# Sheet1.net
KiCad netlist of a schematic drawn in Altium Designer
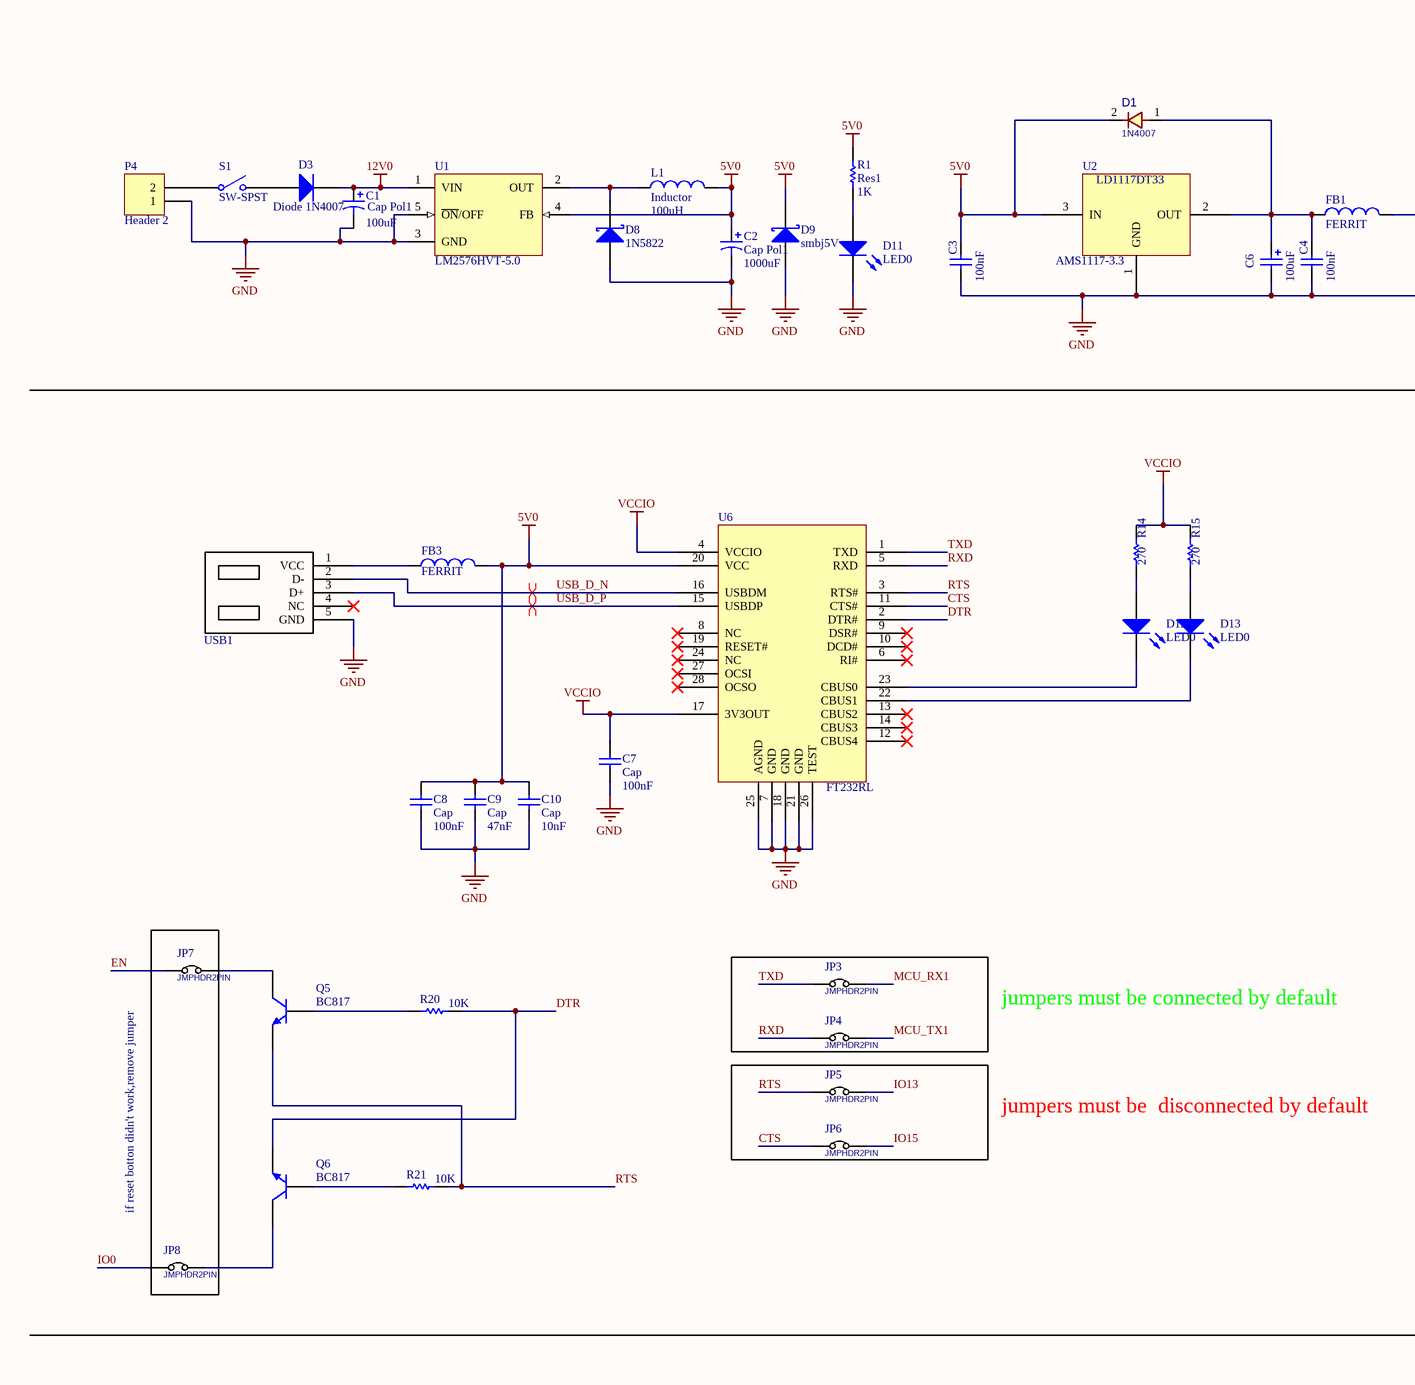
[diagram p0: Sheet1.SchDoc, top left]
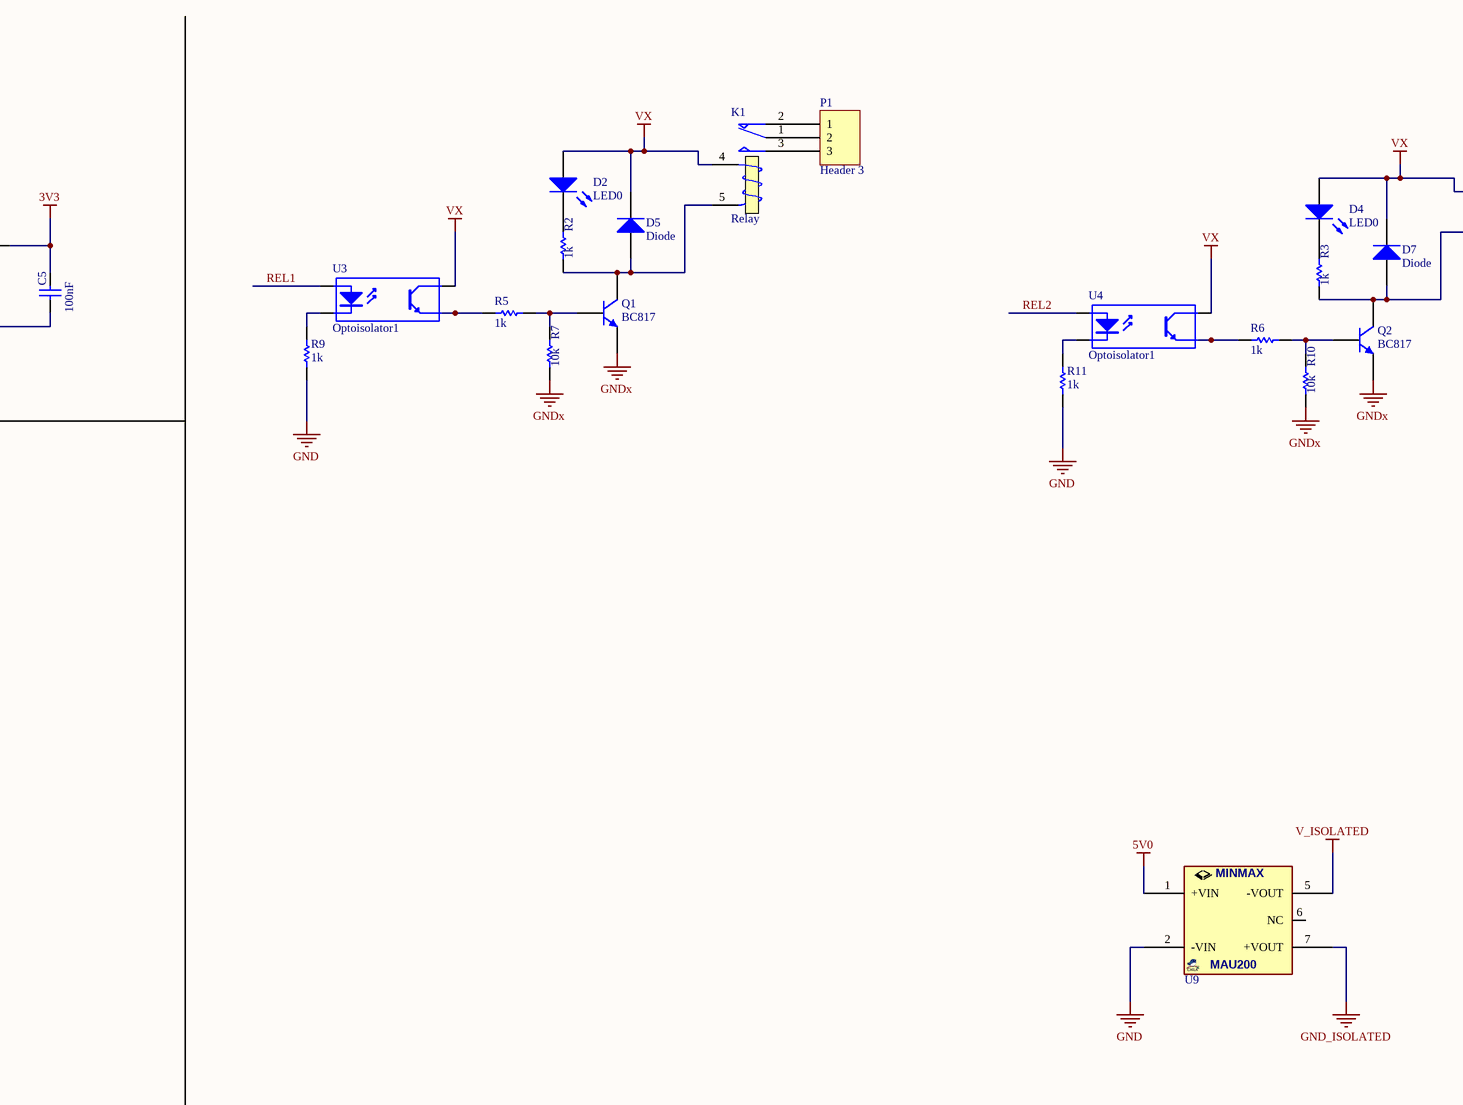
[diagram p1: Sheet1.SchDoc, top middle]
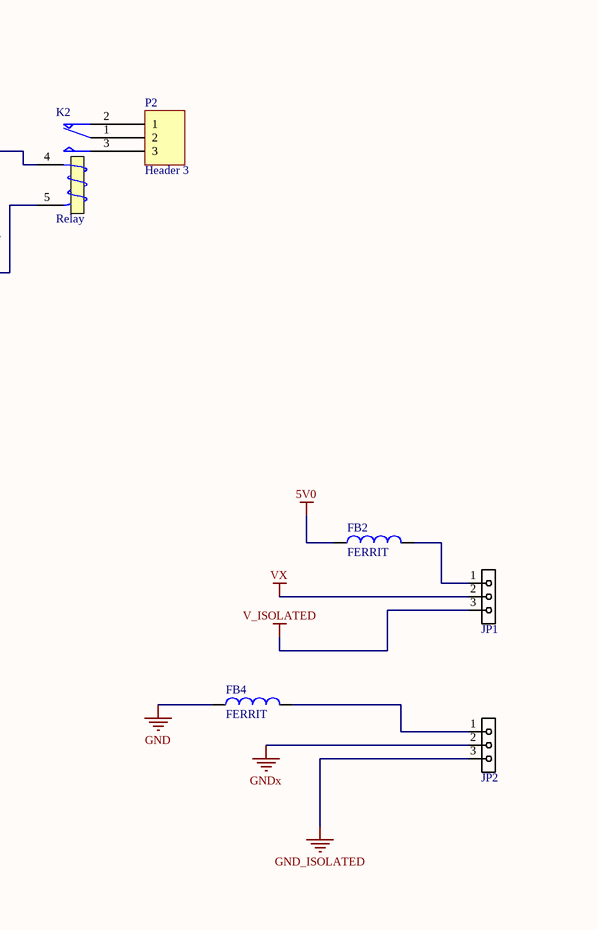
[diagram p2: Sheet1.SchDoc, top right]
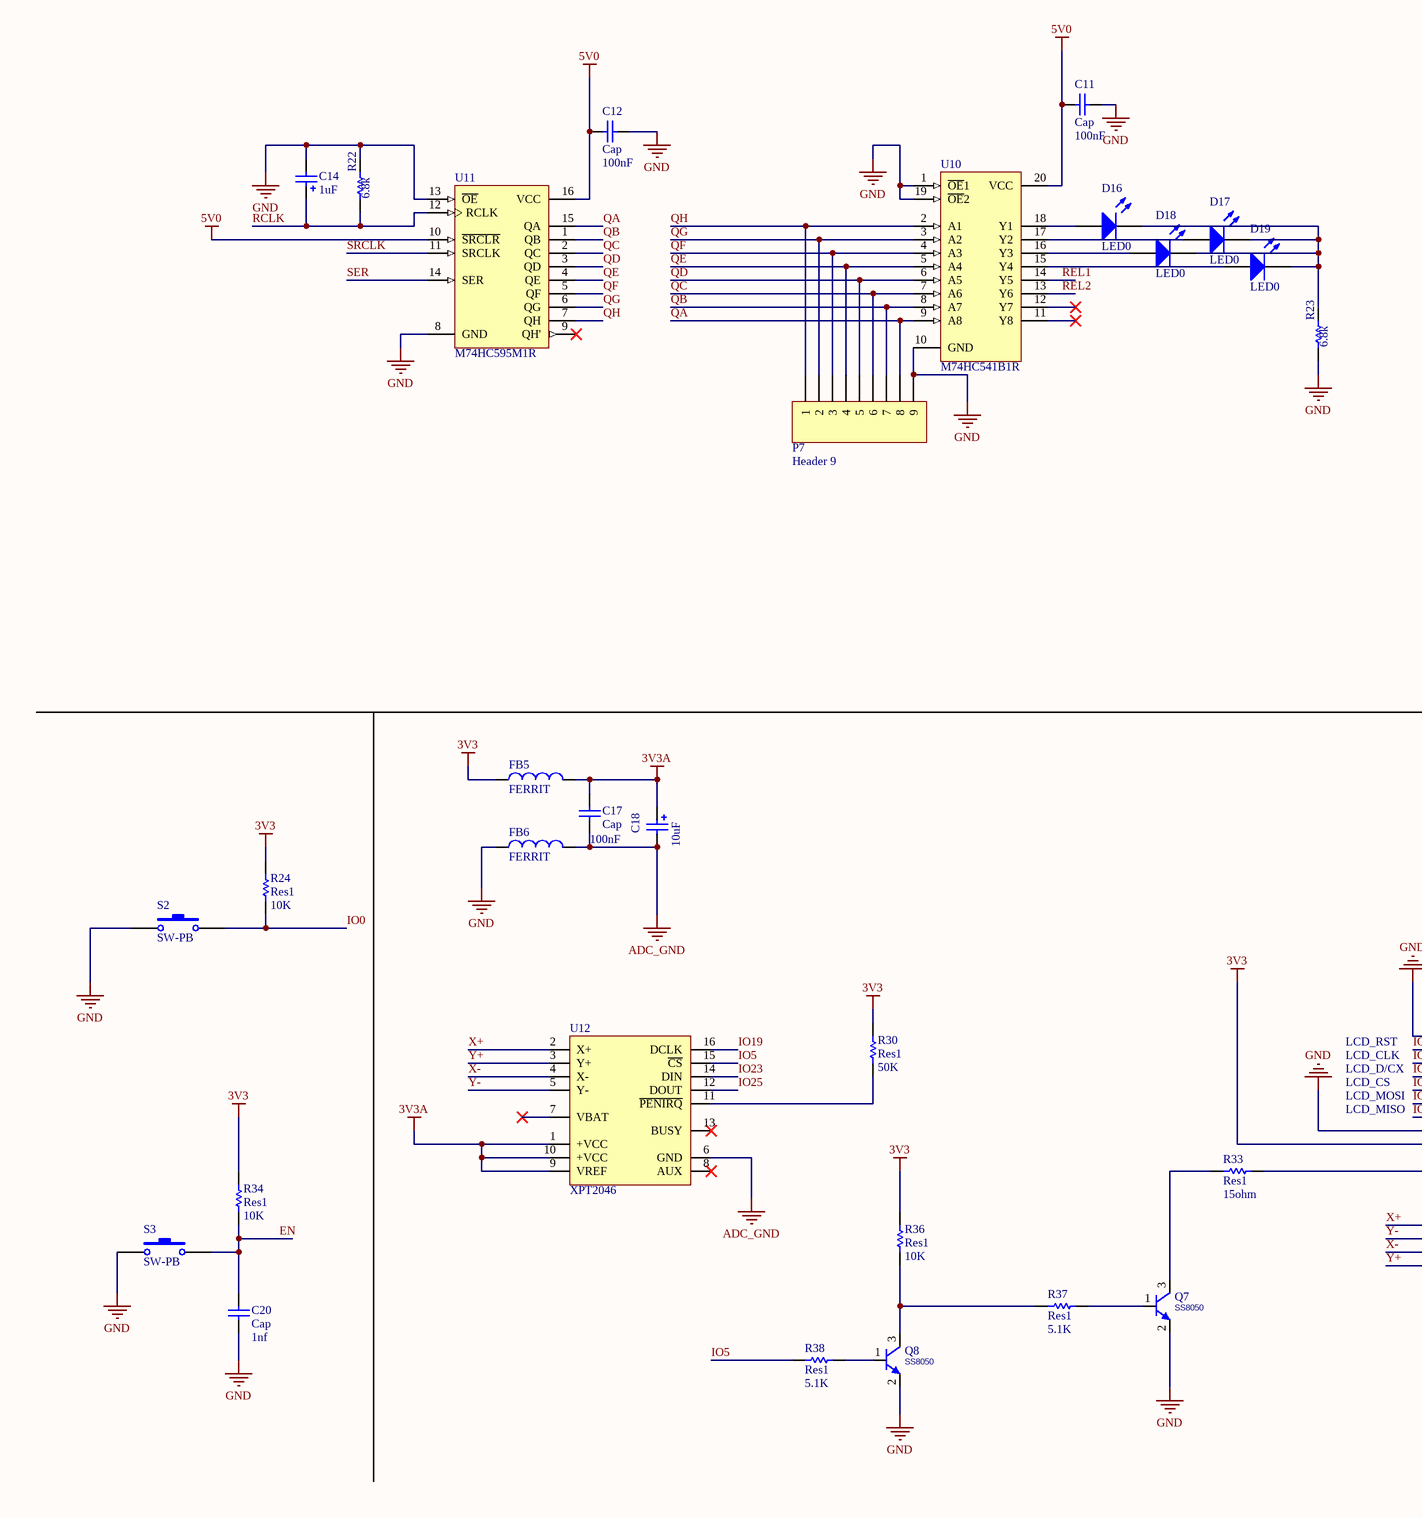
[diagram p3: Sheet1.SchDoc, bottom left]
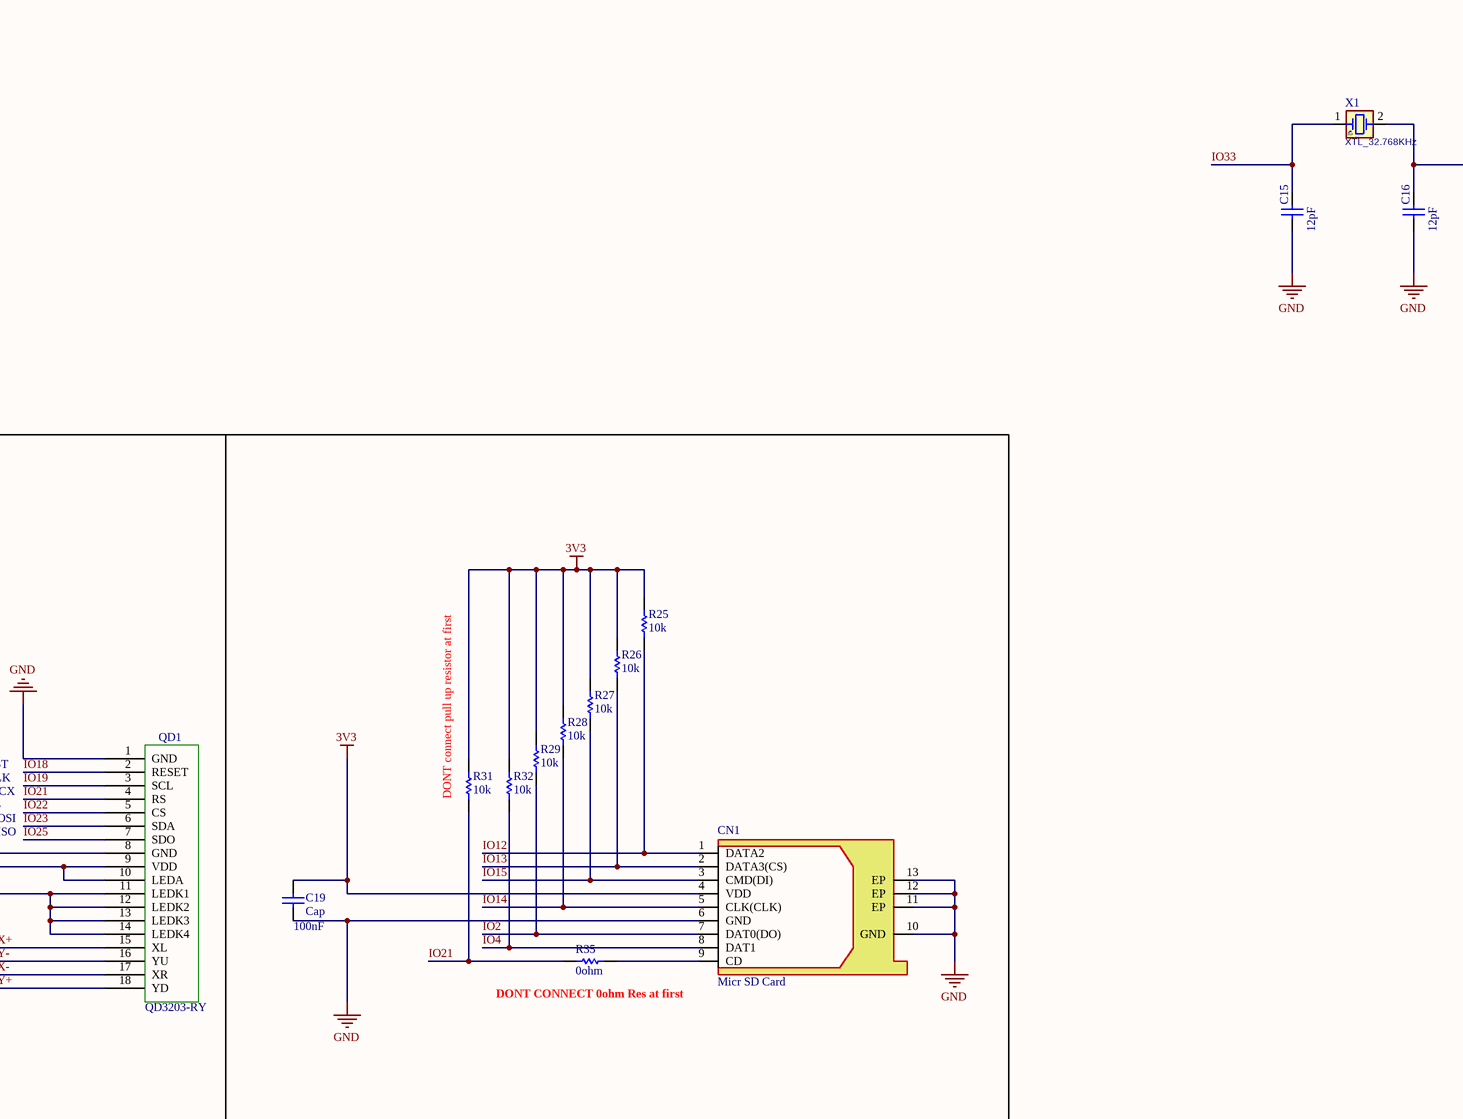
[diagram p4: Sheet1.SchDoc, bottom middle]
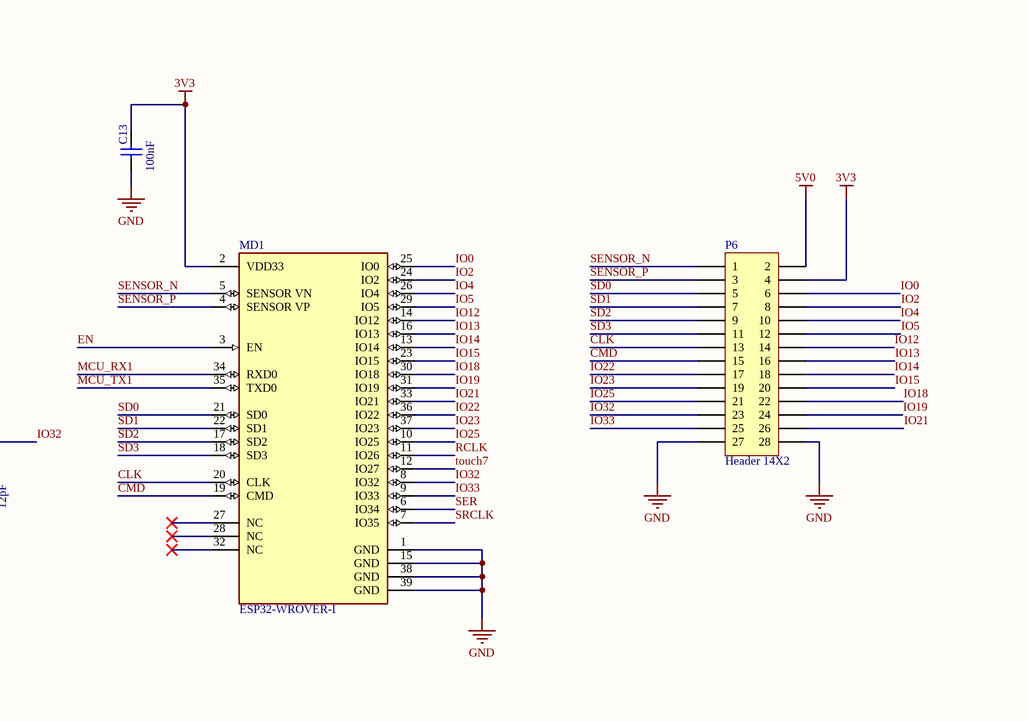
[diagram p5: Sheet1.SchDoc, bottom right]

(export (version "E")
  (design (tool "Eeschema 10.0.6"))
  (components
    (comp (ref "C1")
      (value "Cap Pol1")
      (footprint "C_CYL_SMD2")
      (description "Polarized Capacitor (Radial)")
      (fields (field (name "ALTIUM_VALUE") "100uF") (field (name "PUBLISHER") "Altium Limited"))
      (libsource (lib "Miscellaneous Devices") (part "Cap Pol1"))
    )
    (comp (ref "C2")
      (value "Cap Pol1")
      (footprint "C_CYL_SMD")
      (description "Polarized Capacitor (Radial)")
      (fields (field (name "ALTIUM_VALUE") "1000uF") (field (name "PUBLISHER") "Altium Limited"))
      (libsource (lib "Miscellaneous Devices") (part "Cap Pol1"))
    )
    (comp (ref "C3")
      (value "100nF")
      (footprint "SMD_805")
      (description "Capacitor")
      (fields (field (name "Comment") "Cap") (field (name "PUBLISHER") "Altium Limited"))
      (libsource (lib "Miscellaneous Devices") (part "Cap"))
    )
    (comp (ref "C4")
      (value "100nF")
      (footprint "SMD_805")
      (description "Capacitor")
      (fields (field (name "Comment") "Cap") (field (name "PUBLISHER") "Altium Limited"))
      (libsource (lib "Miscellaneous Devices") (part "Cap"))
    )
    (comp (ref "C5")
      (value "100nF")
      (footprint "SMD_805")
      (description "Capacitor")
      (fields (field (name "Comment") "Cap") (field (name "PUBLISHER") "Altium Limited"))
      (libsource (lib "Miscellaneous Devices") (part "Cap"))
    )
    (comp (ref "C6")
      (value "100uF")
      (footprint "C_B")
      (description "Polarized Capacitor (Axial)")
      (fields (field (name "Comment") "Cap Pol2") (field (name "PUBLISHER") "Altium Limited"))
      (libsource (lib "Miscellaneous Devices") (part "Cap Pol2"))
    )
    (comp (ref "C7")
      (value "Cap")
      (footprint "SMD_805")
      (description "Capacitor")
      (fields (field (name "ALTIUM_VALUE") "100nF") (field (name "PUBLISHER") "Altium Limited"))
      (libsource (lib "Miscellaneous Devices") (part "Cap"))
    )
    (comp (ref "C8")
      (value "Cap")
      (footprint "SMD_805")
      (description "Capacitor")
      (fields (field (name "ALTIUM_VALUE") "100nF") (field (name "PUBLISHER") "Altium Limited"))
      (libsource (lib "Miscellaneous Devices") (part "Cap"))
    )
    (comp (ref "C9")
      (value "Cap")
      (footprint "SMD_805")
      (description "Capacitor")
      (fields (field (name "ALTIUM_VALUE") "47nF") (field (name "PUBLISHER") "Altium Limited"))
      (libsource (lib "Miscellaneous Devices") (part "Cap"))
    )
    (comp (ref "C10")
      (value "Cap")
      (footprint "SMD_805")
      (description "Capacitor")
      (fields (field (name "ALTIUM_VALUE") "10nF") (field (name "PUBLISHER") "Altium Limited"))
      (libsource (lib "Miscellaneous Devices") (part "Cap"))
    )
    (comp (ref "C11")
      (value "Cap")
      (footprint "SMD_805")
      (description "Capacitor")
      (fields (field (name "ALTIUM_VALUE") "100nF") (field (name "PUBLISHER") "Altium Limited"))
      (libsource (lib "Miscellaneous Devices") (part "Cap"))
    )
    (comp (ref "C12")
      (value "Cap")
      (footprint "SMD_805")
      (description "Capacitor")
      (fields (field (name "ALTIUM_VALUE") "100nF") (field (name "PUBLISHER") "Altium Limited"))
      (libsource (lib "Miscellaneous Devices") (part "Cap"))
    )
    (comp (ref "C13")
      (value "100nF")
      (footprint "SMD_805")
      (description "Capacitor")
      (fields (field (name "Comment") "Cap") (field (name "PUBLISHER") "Altium Limited"))
      (libsource (lib "Miscellaneous Devices") (part "Cap"))
    )
    (comp (ref "C14")
      (value "1uF")
      (footprint "CAP_SMD_A")
      (description "Polarized Capacitor (Axial)")
      (fields (field (name "Comment") "Cap Pol2") (field (name "PUBLISHER") "Altium Limited"))
      (libsource (lib "Miscellaneous Devices") (part "Cap Pol2"))
    )
    (comp (ref "C15")
      (value "12pF")
      (footprint "SMD_805")
      (description "Capacitor")
      (fields (field (name "Comment") "Cap") (field (name "PUBLISHER") "Altium Limited"))
      (libsource (lib "Miscellaneous Devices") (part "Cap"))
    )
    (comp (ref "C16")
      (value "12pF")
      (footprint "SMD_805")
      (description "Capacitor")
      (fields (field (name "Comment") "Cap") (field (name "PUBLISHER") "Altium Limited"))
      (libsource (lib "Miscellaneous Devices") (part "Cap"))
    )
    (comp (ref "C17")
      (value "Cap")
      (footprint "SMD_805")
      (description "Capacitor")
      (fields (field (name "ALTIUM_VALUE") "100nF") (field (name "PUBLISHER") "Altium Limited"))
      (libsource (lib "Miscellaneous Devices") (part "Cap"))
    )
    (comp (ref "C18")
      (value "10uF")
      (footprint "C_B")
      (description "Polarized Capacitor (Axial)")
      (fields (field (name "Comment") "Cap Pol2") (field (name "PUBLISHER") "Altium Limited"))
      (libsource (lib "Miscellaneous Devices") (part "Cap Pol2"))
    )
    (comp (ref "C19")
      (value "Cap")
      (footprint "SMD_805")
      (description "Capacitor")
      (fields (field (name "ALTIUM_VALUE") "100nF") (field (name "PUBLISHER") "Altium Limited"))
      (libsource (lib "Miscellaneous Devices") (part "Cap"))
    )
    (comp (ref "C20")
      (value "Cap")
      (footprint "SMD_805")
      (description "Capacitor")
      (fields (field (name "ALTIUM_VALUE") "1nf") (field (name "PUBLISHER") "Altium Limited"))
      (libsource (lib "Miscellaneous Devices") (part "Cap"))
    )
    (comp (ref "CN1")
      (value "Micr SD Card")
      (footprint "Micro SD Card")
      (libsource (lib "ZetaBoard_Lib") (part "Micro SD Card"))
    )
    (comp (ref "D1")
      (value "1N4007")
      (footprint "D_SMA")
      (description "DIODE, GENERAL PURPOSE, 1000V/1A")
      (fields (field (name "MANF") "Kingtronics") (field (name "MANF_P#") "M7"))
      (libsource (lib "diode") (part "DIODE_SMD_1N4007"))
    )
    (comp (ref "D2")
      (value "LED0")
      (footprint "SMD_805")
      (description "Typical INFRARED GaAs LED")
      (fields (field (name "PUBLISHER") "Altium Limited"))
      (libsource (lib "ESP32_project") (part "LED0"))
    )
    (comp (ref "D3")
      (value "Diode 1N4007")
      (footprint "TVS")
      (description "1 Amp General Purpose Rectifier")
      (fields (field (name "PUBLISHER") "Altium Limited"))
      (libsource (lib "Miscellaneous Devices") (part "Diode 1N4007"))
    )
    (comp (ref "D4")
      (value "LED0")
      (footprint "SMD_805")
      (description "Typical INFRARED GaAs LED")
      (fields (field (name "PUBLISHER") "Altium Limited"))
      (libsource (lib "ESP32_project") (part "LED0"))
    )
    (comp (ref "D5")
      (value "Diode")
      (footprint "TVS")
      (description "Default Diode")
      (fields (field (name "PUBLISHER") "Altium Limited"))
      (libsource (lib "Miscellaneous Devices") (part "Diode"))
    )
    (comp (ref "D7")
      (value "Diode")
      (footprint "TVS")
      (description "Default Diode")
      (fields (field (name "PUBLISHER") "Altium Limited"))
      (libsource (lib "Miscellaneous Devices") (part "Diode"))
    )
    (comp (ref "D8")
      (value "1N5822")
      (footprint "DO_214_AB_SMC")
      (description "Schottky Rectifier")
      (fields (field (name "PUBLISHER") "Altium Limited"))
      (libsource (lib "Miscellaneous Devices") (part "Diode 11DQ03"))
    )
    (comp (ref "D9")
      (value "smbj5V")
      (footprint "DO_214_AB_SMC")
      (description "Schottky Rectifier")
      (fields (field (name "PUBLISHER") "Altium Limited"))
      (libsource (lib "Miscellaneous Devices") (part "Diode 11DQ03"))
    )
    (comp (ref "D11")
      (value "LED0")
      (footprint "SMD_805")
      (description "Typical INFRARED GaAs LED")
      (fields (field (name "PUBLISHER") "Altium Limited"))
      (libsource (lib "ESP32_project") (part "LED0"))
    )
    (comp (ref "D12")
      (value "LED0")
      (footprint "SMD_805")
      (description "Typical INFRARED GaAs LED")
      (fields (field (name "PUBLISHER") "Altium Limited"))
      (libsource (lib "ESP32_project") (part "LED0"))
    )
    (comp (ref "D13")
      (value "LED0")
      (footprint "SMD_805")
      (description "Typical INFRARED GaAs LED")
      (fields (field (name "PUBLISHER") "Altium Limited"))
      (libsource (lib "ESP32_project") (part "LED0"))
    )
    (comp (ref "D16")
      (value "LED0")
      (footprint "SMD_805")
      (description "Typical INFRARED GaAs LED")
      (fields (field (name "PUBLISHER") "Altium Limited"))
      (libsource (lib "ESP32_project") (part "LED0"))
    )
    (comp (ref "D17")
      (value "LED0")
      (footprint "SMD_805")
      (description "Typical INFRARED GaAs LED")
      (fields (field (name "PUBLISHER") "Altium Limited"))
      (libsource (lib "ESP32_project") (part "LED0"))
    )
    (comp (ref "D18")
      (value "LED0")
      (footprint "SMD_805")
      (description "Typical INFRARED GaAs LED")
      (fields (field (name "PUBLISHER") "Altium Limited"))
      (libsource (lib "ESP32_project") (part "LED0"))
    )
    (comp (ref "D19")
      (value "LED0")
      (footprint "SMD_805")
      (description "Typical INFRARED GaAs LED")
      (fields (field (name "PUBLISHER") "Altium Limited"))
      (libsource (lib "ESP32_project") (part "LED0"))
    )
    (comp (ref "FB1")
      (value "FERRIT")
      (footprint "SMD_805")
      (description "Inductor")
      (fields (field (name "PUBLISHER") "Altium Limited"))
      (libsource (lib "Miscellaneous Devices") (part "Inductor"))
    )
    (comp (ref "FB2")
      (value "FERRIT")
      (footprint "SMD_805")
      (description "Inductor")
      (fields (field (name "PUBLISHER") "Altium Limited"))
      (libsource (lib "Miscellaneous Devices") (part "Inductor"))
    )
    (comp (ref "FB3")
      (value "FERRIT")
      (footprint "SMD_805")
      (description "Inductor")
      (fields (field (name "PUBLISHER") "Altium Limited"))
      (libsource (lib "Miscellaneous Devices") (part "Inductor"))
    )
    (comp (ref "FB4")
      (value "FERRIT")
      (footprint "SMD_805")
      (description "Inductor")
      (fields (field (name "PUBLISHER") "Altium Limited"))
      (libsource (lib "Miscellaneous Devices") (part "Inductor"))
    )
    (comp (ref "FB5")
      (value "FERRIT")
      (footprint "SMD_805")
      (description "Inductor")
      (fields (field (name "PUBLISHER") "Altium Limited"))
      (libsource (lib "Miscellaneous Devices") (part "Inductor"))
    )
    (comp (ref "FB6")
      (value "FERRIT")
      (footprint "SMD_805")
      (description "Inductor")
      (fields (field (name "PUBLISHER") "Altium Limited"))
      (libsource (lib "Miscellaneous Devices") (part "Inductor"))
    )
    (comp (ref "JP1")
      (value "JMPHDR3PIN")
      (footprint "JP_3")
      (description "JUMPER, HEADER 3PIN")
      (fields (field (name "MANF") "MANF") (field (name "MANF_P#") "MANF_P#"))
      (libsource (lib "test-tp_jumper") (part "JUMPER_HDR_3P"))
    )
    (comp (ref "JP2")
      (value "JMPHDR3PIN")
      (footprint "JP_3")
      (description "JUMPER, HEADER 3PIN")
      (fields (field (name "MANF") "MANF") (field (name "MANF_P#") "MANF_P#"))
      (libsource (lib "test-tp_jumper") (part "JUMPER_HDR_3P"))
    )
    (comp (ref "JP3")
      (value "JMPHDR2PIN")
      (footprint "JP_2_BLK")
      (description "JUMPER, HEADER 2PIN")
      (fields (field (name "MANF") "MANF") (field (name "MANF_P#") "MANF_P#"))
      (libsource (lib "test-tp_jumper") (part "JUMPER_HDR_2P"))
    )
    (comp (ref "JP4")
      (value "JMPHDR2PIN")
      (footprint "JP_2_BLK")
      (description "JUMPER, HEADER 2PIN")
      (fields (field (name "MANF") "MANF") (field (name "MANF_P#") "MANF_P#"))
      (libsource (lib "test-tp_jumper") (part "JUMPER_HDR_2P"))
    )
    (comp (ref "JP5")
      (value "JMPHDR2PIN")
      (footprint "JP_2_BLK")
      (description "JUMPER, HEADER 2PIN")
      (fields (field (name "MANF") "MANF") (field (name "MANF_P#") "MANF_P#"))
      (libsource (lib "test-tp_jumper") (part "JUMPER_HDR_2P"))
    )
    (comp (ref "JP6")
      (value "JMPHDR2PIN")
      (footprint "JP_2_BLK")
      (description "JUMPER, HEADER 2PIN")
      (fields (field (name "MANF") "MANF") (field (name "MANF_P#") "MANF_P#"))
      (libsource (lib "test-tp_jumper") (part "JUMPER_HDR_2P"))
    )
    (comp (ref "JP7")
      (value "JMPHDR2PIN")
      (footprint "JP_2_BLK")
      (description "JUMPER, HEADER 2PIN")
      (fields (field (name "MANF") "MANF") (field (name "MANF_P#") "MANF_P#"))
      (libsource (lib "test-tp_jumper") (part "JUMPER_HDR_2P"))
    )
    (comp (ref "JP8")
      (value "JMPHDR2PIN")
      (footprint "JP_2_BLK")
      (description "JUMPER, HEADER 2PIN")
      (fields (field (name "MANF") "MANF") (field (name "MANF_P#") "MANF_P#"))
      (libsource (lib "test-tp_jumper") (part "JUMPER_HDR_2P"))
    )
    (comp (ref "K1")
      (value "Relay")
      (footprint "RELAY_5V")
      (description "SPDT Relay")
      (fields (field (name "PUBLISHER") "Altium Limited"))
      (libsource (lib "Miscellaneous Devices") (part "Relay"))
    )
    (comp (ref "K2")
      (value "Relay")
      (footprint "RELAY_5V")
      (description "SPDT Relay")
      (fields (field (name "PUBLISHER") "Altium Limited"))
      (libsource (lib "Miscellaneous Devices") (part "Relay"))
    )
    (comp (ref "L1")
      (value "Inductor")
      (footprint "INDUC_SMD")
      (fields (field (name "ALTIUM_VALUE") "100uH") (field (name "PUBLISHER") "Altium Limited"))
      (libsource (lib "Miscellaneous Devices") (part "Inductor"))
    )
    (comp (ref "MD1")
      (value "ESP32-WROVER-I")
      (footprint "FP-ESP32-WROVER-I-MFG")
      (description "SMD MODULE, ESP32-D0WDQ6, 32MBIT")
      (fields
        (field (name "MANUFACTURER") "Espressif")
        (field (name "OCTOPART") "https://octopart.com/esp32-wrover-i-espressif+systems-89171349")
      )
      (libsource (lib "Altium Content Vault") (part "cbbb37af8bcfe61dfd46ac9418f0340"))
    )
    (comp (ref "P1")
      (value "Header 3")
      (footprint "PHOENIX_3")
      (description "Header, 3-Pin")
      (fields (field (name "PUBLISHER") "Altium Limited"))
      (libsource (lib "Miscellaneous Connectors") (part "Header 3"))
    )
    (comp (ref "P2")
      (value "Header 3")
      (footprint "PHOENIX_3")
      (description "Header, 3-Pin")
      (fields (field (name "PUBLISHER") "Altium Limited"))
      (libsource (lib "Miscellaneous Connectors") (part "Header 3"))
    )
    (comp (ref "P4")
      (value "Header 2")
      (footprint "adap_jack")
      (description "Header, 2-Pin")
      (fields (field (name "PUBLISHER") "Altium Limited"))
      (libsource (lib "Miscellaneous Connectors") (part "Header 2"))
    )
    (comp (ref "P6")
      (value "Header 14X2")
      (footprint "HDR2X14")
      (description "Header, 14-Pin, Dual row")
      (fields (field (name "PUBLISHER") "Altium Limited"))
      (libsource (lib "Miscellaneous Connectors") (part "Header 14X2"))
    )
    (comp (ref "P7")
      (value "Header 9")
      (footprint "ARAY 9")
      (description "Header, 9-Pin")
      (fields (field (name "PUBLISHER") "Altium Limited"))
      (libsource (lib "Miscellaneous Connectors") (part "Header 9"))
    )
    (comp (ref "Q1")
      (value "BC817")
      (footprint "SOT23")
      (description "NPN General Purpose Amplifier")
      (fields (field (name "PUBLISHER") "Altium Limited"))
      (libsource (lib "Miscellaneous Devices") (part "2N3904"))
    )
    (comp (ref "Q2")
      (value "BC817")
      (footprint "SOT23")
      (description "NPN General Purpose Amplifier")
      (fields (field (name "PUBLISHER") "Altium Limited"))
      (libsource (lib "Miscellaneous Devices") (part "2N3904"))
    )
    (comp (ref "Q5")
      (value "BC817")
      (footprint "SOT23")
      (description "NPN General Purpose Amplifier")
      (fields (field (name "PUBLISHER") "Altium Limited"))
      (libsource (lib "Miscellaneous Devices") (part "2N3904"))
    )
    (comp (ref "Q6")
      (value "BC817")
      (footprint "SOT23")
      (description "NPN General Purpose Amplifier")
      (fields (field (name "PUBLISHER") "Altium Limited"))
      (libsource (lib "Miscellaneous Devices") (part "2N3904"))
    )
    (comp (ref "Q7")
      (value "SS8050")
      (footprint "SOT23_3")
      (description "BJT, NPN, 25v, 1.5A, SMD, SOT23")
      (fields (field (name "MANF") "GALAXY"))
      (libsource (lib "transistor_bjt") (part "NPN_SS8050_SOT23"))
    )
    (comp (ref "Q8")
      (value "SS8050")
      (footprint "SOT23_3")
      (description "BJT, NPN, 25v, 1.5A, SMD, SOT23")
      (fields (field (name "MANF") "GALAXY"))
      (libsource (lib "transistor_bjt") (part "NPN_SS8050_SOT23"))
    )
    (comp (ref "QD1")
      (value "QD3203-RY")
      (footprint "QD-TFT2803")
      (libsource (lib "2.8inch_MSP2807_Schematic_Package_Library") (part "FPC240A8230-V1-E"))
    )
    (comp (ref "R1")
      (value "Res1")
      (footprint "SMD_805")
      (description "Resistor")
      (fields (field (name "ALTIUM_VALUE") "1K") (field (name "PUBLISHER") "Altium Limited"))
      (libsource (lib "Miscellaneous Devices") (part "Res1"))
    )
    (comp (ref "R2")
      (value "1k")
      (footprint "SMD_805")
      (description "Resistor")
      (fields (field (name "Comment") "Res1") (field (name "PUBLISHER") "Altium Limited"))
      (libsource (lib "Miscellaneous Devices") (part "Res1"))
    )
    (comp (ref "R3")
      (value "1k")
      (footprint "SMD_805")
      (description "Resistor")
      (fields (field (name "Comment") "Res1") (field (name "PUBLISHER") "Altium Limited"))
      (libsource (lib "Miscellaneous Devices") (part "Res1"))
    )
    (comp (ref "R5")
      (value "1k")
      (footprint "SMD_805")
      (description "Resistor")
      (fields (field (name "Comment") "Res1") (field (name "PUBLISHER") "Altium Limited"))
      (libsource (lib "Miscellaneous Devices") (part "Res1"))
    )
    (comp (ref "R6")
      (value "1k")
      (footprint "SMD_805")
      (description "Resistor")
      (fields (field (name "Comment") "Res1") (field (name "PUBLISHER") "Altium Limited"))
      (libsource (lib "Miscellaneous Devices") (part "Res1"))
    )
    (comp (ref "R7")
      (value "10k")
      (footprint "SMD_805")
      (description "Resistor")
      (fields (field (name "Comment") "Res1") (field (name "PUBLISHER") "Altium Limited"))
      (libsource (lib "Miscellaneous Devices") (part "Res1"))
    )
    (comp (ref "R9")
      (value "1k")
      (footprint "SMD_805")
      (description "Resistor")
      (fields (field (name "Comment") "Res1") (field (name "PUBLISHER") "Altium Limited"))
      (libsource (lib "Miscellaneous Devices") (part "Res1"))
    )
    (comp (ref "R10")
      (value "10k")
      (footprint "SMD_805")
      (description "Resistor")
      (fields (field (name "Comment") "Res1") (field (name "PUBLISHER") "Altium Limited"))
      (libsource (lib "Miscellaneous Devices") (part "Res1"))
    )
    (comp (ref "R11")
      (value "1k")
      (footprint "SMD_805")
      (description "Resistor")
      (fields (field (name "Comment") "Res1") (field (name "PUBLISHER") "Altium Limited"))
      (libsource (lib "Miscellaneous Devices") (part "Res1"))
    )
    (comp (ref "R14")
      (value "270")
      (footprint "SMD_805")
      (description "Resistor")
      (fields (field (name "Comment") "Res1") (field (name "PUBLISHER") "Altium Limited"))
      (libsource (lib "Miscellaneous Devices") (part "Res1"))
    )
    (comp (ref "R15")
      (value "270")
      (footprint "SMD_805")
      (description "Resistor")
      (fields (field (name "Comment") "Res1") (field (name "PUBLISHER") "Altium Limited"))
      (libsource (lib "Miscellaneous Devices") (part "Res1"))
    )
    (comp (ref "R20")
      (value "10K")
      (footprint "SMD_805")
      (description "Resistor")
      (fields (field (name "Comment") "Res1") (field (name "PUBLISHER") "Altium Limited"))
      (libsource (lib "Miscellaneous Devices") (part "Res1"))
    )
    (comp (ref "R21")
      (value "10K")
      (footprint "SMD_805")
      (description "Resistor")
      (fields (field (name "Comment") "Res1") (field (name "PUBLISHER") "Altium Limited"))
      (libsource (lib "Miscellaneous Devices") (part "Res1"))
    )
    (comp (ref "R22")
      (value "6.8k")
      (footprint "SMD_805")
      (description "Resistor")
      (fields (field (name "Comment") "Res1") (field (name "PUBLISHER") "Altium Limited"))
      (libsource (lib "Miscellaneous Devices") (part "Res1"))
    )
    (comp (ref "R23")
      (value "6.8k")
      (footprint "SMD_805")
      (description "Resistor")
      (fields (field (name "Comment") "Res1") (field (name "PUBLISHER") "Altium Limited"))
      (libsource (lib "Miscellaneous Devices") (part "Res1"))
    )
    (comp (ref "R24")
      (value "Res1")
      (footprint "SMD_805")
      (description "Resistor")
      (fields (field (name "ALTIUM_VALUE") "10K") (field (name "PUBLISHER") "Altium Limited"))
      (libsource (lib "Miscellaneous Devices") (part "Res1"))
    )
    (comp (ref "R25")
      (value "10k")
      (footprint "SMD_805")
      (description "Resistor")
      (fields (field (name "Comment") "Res1") (field (name "PUBLISHER") "Altium Limited"))
      (libsource (lib "Miscellaneous Devices") (part "Res1"))
    )
    (comp (ref "R26")
      (value "10k")
      (footprint "SMD_805")
      (description "Resistor")
      (fields (field (name "Comment") "Res1") (field (name "PUBLISHER") "Altium Limited"))
      (libsource (lib "Miscellaneous Devices") (part "Res1"))
    )
    (comp (ref "R27")
      (value "10k")
      (footprint "SMD_805")
      (description "Resistor")
      (fields (field (name "Comment") "Res1") (field (name "PUBLISHER") "Altium Limited"))
      (libsource (lib "Miscellaneous Devices") (part "Res1"))
    )
    (comp (ref "R28")
      (value "10k")
      (footprint "SMD_805")
      (description "Resistor")
      (fields (field (name "Comment") "Res1") (field (name "PUBLISHER") "Altium Limited"))
      (libsource (lib "Miscellaneous Devices") (part "Res1"))
    )
    (comp (ref "R29")
      (value "10k")
      (footprint "SMD_805")
      (description "Resistor")
      (fields (field (name "Comment") "Res1") (field (name "PUBLISHER") "Altium Limited"))
      (libsource (lib "Miscellaneous Devices") (part "Res1"))
    )
    (comp (ref "R30")
      (value "Res1")
      (footprint "SMD_805")
      (description "Resistor")
      (fields (field (name "ALTIUM_VALUE") "50K") (field (name "PUBLISHER") "Altium Limited"))
      (libsource (lib "Miscellaneous Devices") (part "Res1"))
    )
    (comp (ref "R31")
      (value "10k")
      (footprint "SMD_805")
      (description "Resistor")
      (fields (field (name "Comment") "Res1") (field (name "PUBLISHER") "Altium Limited"))
      (libsource (lib "Miscellaneous Devices") (part "Res1"))
    )
    (comp (ref "R32")
      (value "10k")
      (footprint "SMD_805")
      (description "Resistor")
      (fields (field (name "Comment") "Res1") (field (name "PUBLISHER") "Altium Limited"))
      (libsource (lib "Miscellaneous Devices") (part "Res1"))
    )
    (comp (ref "R33")
      (value "Res1")
      (footprint "SMD_805")
      (description "Resistor")
      (fields (field (name "ALTIUM_VALUE") "15ohm") (field (name "PUBLISHER") "Altium Limited"))
      (libsource (lib "Miscellaneous Devices") (part "Res1"))
    )
    (comp (ref "R34")
      (value "Res1")
      (footprint "SMD_805")
      (description "Resistor")
      (fields (field (name "ALTIUM_VALUE") "10K") (field (name "PUBLISHER") "Altium Limited"))
      (libsource (lib "Miscellaneous Devices") (part "Res1"))
    )
    (comp (ref "R35")
      (value "0ohm")
      (footprint "SMD_805")
      (description "Resistor")
      (fields (field (name "Comment") "Res1") (field (name "PUBLISHER") "Altium Limited"))
      (libsource (lib "Miscellaneous Devices") (part "Res1"))
    )
    (comp (ref "R36")
      (value "Res1")
      (footprint "SMD_805")
      (description "Resistor")
      (fields (field (name "ALTIUM_VALUE") "10K") (field (name "PUBLISHER") "Altium Limited"))
      (libsource (lib "Miscellaneous Devices") (part "Res1"))
    )
    (comp (ref "R37")
      (value "Res1")
      (footprint "SMD_805")
      (description "Resistor")
      (fields (field (name "ALTIUM_VALUE") "5.1K") (field (name "PUBLISHER") "Altium Limited"))
      (libsource (lib "Miscellaneous Devices") (part "Res1"))
    )
    (comp (ref "R38")
      (value "Res1")
      (footprint "SMD_805")
      (description "Resistor")
      (fields (field (name "ALTIUM_VALUE") "5.1K") (field (name "PUBLISHER") "Altium Limited"))
      (libsource (lib "Miscellaneous Devices") (part "Res1"))
    )
    (comp (ref "S1")
      (value "SW-SPST")
      (footprint "KEY1")
      (description "Single-Pole, Single-Throw Switch")
      (fields (field (name "PUBLISHER") "Altium Limited"))
      (libsource (lib "Miscellaneous Devices") (part "SW-SPST"))
    )
    (comp (ref "S2")
      (value "SW-PB")
      (footprint "smd_button")
      (description "Switch")
      (fields (field (name "PUBLISHER") "Altium Limited"))
      (libsource (lib "Miscellaneous Devices") (part "SW-PB"))
    )
    (comp (ref "S3")
      (value "SW-PB")
      (footprint "smd_button")
      (description "Switch")
      (fields (field (name "PUBLISHER") "Altium Limited"))
      (libsource (lib "Miscellaneous Devices") (part "SW-PB"))
    )
    (comp (ref "U1")
      (value "LM2576HVT-5.0")
      (footprint "TO - 263")
      (description "SIMPLE SWITCHER; 3A Step-Down Voltage Regulator")
      (fields
        (field (name "MANUFACTURER") "National Semiconductor")
        (field (name "DIGIKEYPARTNUMBER") "LM2576HVT-5.0-ND")
        (field (name "PUBLISHER") "Altium Limited")
      )
      (libsource (lib "NSC Switcher") (part "LM2576HVT-5.0"))
    )
    (comp (ref "U2")
      (value "AMS1117-3.3")
      (footprint "SOT223")
      (libsource (lib "LD1117DT33") (part "LD1117DT33"))
    )
    (comp (ref "U3")
      (value "Optoisolator1")
      (footprint "PC817_SMD")
      (description "4-Pin Phototransistor Optocoupler")
      (fields (field (name "PUBLISHER") "Altium Limited"))
      (libsource (lib "Miscellaneous Devices") (part "Optoisolator1"))
    )
    (comp (ref "U4")
      (value "Optoisolator1")
      (footprint "PC817_SMD")
      (description "4-Pin Phototransistor Optocoupler")
      (fields (field (name "PUBLISHER") "Altium Limited"))
      (libsource (lib "Miscellaneous Devices") (part "Optoisolator1"))
    )
    (comp (ref "U6") (value "FT232RL") (footprint "SOG65_28_W") (libsource (lib "FT232RL") (part "FT232RL")))
    (comp (ref "U9")
      (value "MAU202")
      (footprint "MINMAX_MAU200")
      (description "DC-DC Converter, Isolated, 1W")
      (fields (field (name "MANF") "MINMAX"))
      (libsource (lib "module_dc2dc_iso") (part "MAU202"))
    )
    (comp (ref "U10")
      (value "M74HC541B1R")
      (footprint "SOP20")
      (description "Octal Bus Buffer with 3 State Outputs (Non Inverted)")
      (fields (field (name "PUBLISHER") "Altium Limited"))
      (libsource (lib "ST Logic Buffer Line Driver") (part "M74HC541B1R"))
    )
    (comp (ref "U11")
      (value "M74HC595M1R")
      (footprint "SO16_L")
      (description "8 Bit Shift Register with Output Latches (3 STATE)")
      (fields (field (name "PUBLISHER") "Altium Limited"))
      (libsource (lib "ST Logic Register") (part "M74HC595M1R"))
    )
    (comp (ref "U12")
      (value "XPT2046")
      (footprint "TSSOP-16")
      (libsource (lib "ZetaBoard_Lib") (part "XPT2046"))
    )
    (comp (ref "USB1")
      (value "MICRO_USB")
      (footprint "MINI_USB")
      (libsource (lib "MICRO_USB") (part "MICRO_USB"))
    )
    (comp (ref "X1")
      (value "XTL_32.768KHz")
      (footprint "XTL_2_1610")
      (description "Crystal, 32.768KHz, 9pF, 20PPM")
      (fields (field (name "MANF") "ABRACON") (field (name "MANF_P#") "ABS05-32.768KHZ-9-T"))
      (libsource (lib "crystal") (part "XTL_2_32.768_1610A"))
    )
  )
  (nets
    (net (code "1") (name "/CLK") (class "Default")
      (node (ref "MD1") (pin "20") (pinfunction "CLK_20") (pintype "bidirectional"))
      (node (ref "P6") (pin "13") (pinfunction "13_13") (pintype "passive"))
    )
    (net (code "2") (name "/CMD") (class "Default")
      (node (ref "MD1") (pin "19") (pinfunction "CMD_19") (pintype "bidirectional"))
      (node (ref "P6") (pin "15") (pinfunction "15_15") (pintype "passive"))
    )
    (net (code "3") (name "/CTS") (class "Default")
      (node (ref "JP6") (pin "1") (pinfunction "1_1") (pintype "passive"))
      (node (ref "U6") (pin "11") (pinfunction "CTS#_11") (pintype "passive"))
    )
    (net (code "4") (name "/DTR") (class "Default")
      (node (ref "Q6") (pin "2") (pinfunction "E_2") (pintype "passive"))
      (node (ref "R20") (pin "1") (pinfunction "1_1") (pintype "passive"))
      (node (ref "U6") (pin "2") (pinfunction "DTR#_2") (pintype "passive"))
    )
    (net (code "5") (name "/EN") (class "Default")
      (node (ref "C20") (pin "2") (pinfunction "2_2") (pintype "passive"))
      (node (ref "JP7") (pin "1") (pinfunction "1_1") (pintype "passive"))
      (node (ref "MD1") (pin "3") (pinfunction "EN_3") (pintype "input"))
      (node (ref "R34") (pin "1") (pinfunction "1_1") (pintype "passive"))
      (node (ref "S3") (pin "2") (pinfunction "2_2") (pintype "passive"))
    )
    (net (code "6") (name "/IO0") (class "Default")
      (node (ref "JP8") (pin "1") (pinfunction "1_1") (pintype "passive"))
      (node (ref "MD1") (pin "25") (pinfunction "IO0_25") (pintype "bidirectional"))
      (node (ref "P6") (pin "6") (pinfunction "6_6") (pintype "passive"))
      (node (ref "R24") (pin "1") (pinfunction "1_1") (pintype "passive"))
      (node (ref "S2") (pin "2") (pinfunction "2_2") (pintype "passive"))
    )
    (net (code "7") (name "/IO2") (class "Default")
      (node (ref "CN1") (pin "7") (pinfunction "DAT0(DO)_7") (pintype "passive"))
      (node (ref "MD1") (pin "24") (pinfunction "IO2_24") (pintype "bidirectional"))
      (node (ref "P6") (pin "8") (pinfunction "8_8") (pintype "passive"))
      (node (ref "R29") (pin "2") (pinfunction "2_2") (pintype "passive"))
    )
    (net (code "8") (name "/IO4") (class "Default")
      (node (ref "CN1") (pin "8") (pinfunction "DAT1_8") (pintype "passive"))
      (node (ref "MD1") (pin "26") (pinfunction "IO4_26") (pintype "bidirectional"))
      (node (ref "P6") (pin "10") (pinfunction "10_10") (pintype "passive"))
      (node (ref "R32") (pin "2") (pinfunction "2_2") (pintype "passive"))
    )
    (net (code "9") (name "/IO5") (class "Default")
      (node (ref "MD1") (pin "29") (pinfunction "IO5_29") (pintype "bidirectional"))
      (node (ref "P6") (pin "12") (pinfunction "12_12") (pintype "passive"))
      (node (ref "R38") (pin "2") (pinfunction "2_2") (pintype "passive"))
      (node (ref "U12") (pin "15") (pinfunction "~{CS}_15") (pintype "passive"))
    )
    (net (code "10") (name "/IO12") (class "Default")
      (node (ref "CN1") (pin "1") (pinfunction "DATA2_1") (pintype "passive"))
      (node (ref "MD1") (pin "14") (pinfunction "IO12_14") (pintype "bidirectional"))
      (node (ref "P6") (pin "14") (pinfunction "14_14") (pintype "passive"))
      (node (ref "R25") (pin "2") (pinfunction "2_2") (pintype "passive"))
    )
    (net (code "11") (name "/IO13") (class "Default")
      (node (ref "CN1") (pin "2") (pinfunction "DATA3(CS)_2") (pintype "passive"))
      (node (ref "JP5") (pin "2") (pinfunction "2_2") (pintype "passive"))
      (node (ref "MD1") (pin "16") (pinfunction "IO13_16") (pintype "bidirectional"))
      (node (ref "P6") (pin "16") (pinfunction "16_16") (pintype "passive"))
      (node (ref "R26") (pin "2") (pinfunction "2_2") (pintype "passive"))
    )
    (net (code "12") (name "/IO14") (class "Default")
      (node (ref "CN1") (pin "5") (pinfunction "CLK(CLK)_5") (pintype "passive"))
      (node (ref "MD1") (pin "13") (pinfunction "IO14_13") (pintype "bidirectional"))
      (node (ref "P6") (pin "18") (pinfunction "18_18") (pintype "passive"))
      (node (ref "R28") (pin "2") (pinfunction "2_2") (pintype "passive"))
    )
    (net (code "13") (name "/IO15") (class "Default")
      (node (ref "CN1") (pin "3") (pinfunction "CMD(DI)_3") (pintype "passive"))
      (node (ref "JP6") (pin "2") (pinfunction "2_2") (pintype "passive"))
      (node (ref "MD1") (pin "23") (pinfunction "IO15_23") (pintype "bidirectional"))
      (node (ref "P6") (pin "20") (pinfunction "20_20") (pintype "passive"))
      (node (ref "R27") (pin "2") (pinfunction "2_2") (pintype "passive"))
    )
    (net (code "14") (name "/IO18") (class "Default")
      (node (ref "MD1") (pin "30") (pinfunction "IO18_30") (pintype "bidirectional"))
      (node (ref "P6") (pin "22") (pinfunction "22_22") (pintype "passive"))
      (node (ref "QD1") (pin "2") (pinfunction "RESET_2") (pintype "passive"))
    )
    (net (code "15") (name "/IO19") (class "Default")
      (node (ref "MD1") (pin "31") (pinfunction "IO19_31") (pintype "bidirectional"))
      (node (ref "P6") (pin "24") (pinfunction "24_24") (pintype "passive"))
      (node (ref "QD1") (pin "3") (pinfunction "SCL_3") (pintype "passive"))
      (node (ref "U12") (pin "16") (pinfunction "DCLK_16") (pintype "passive"))
    )
    (net (code "16") (name "/IO21") (class "Default")
      (node (ref "MD1") (pin "33") (pinfunction "IO21_33") (pintype "bidirectional"))
      (node (ref "P6") (pin "26") (pinfunction "26_26") (pintype "passive"))
      (node (ref "QD1") (pin "4") (pinfunction "RS_4") (pintype "passive"))
      (node (ref "R31") (pin "2") (pinfunction "2_2") (pintype "passive"))
      (node (ref "R35") (pin "1") (pinfunction "1_1") (pintype "passive"))
    )
    (net (code "17") (name "/IO22") (class "Default")
      (node (ref "MD1") (pin "36") (pinfunction "IO22_36") (pintype "bidirectional"))
      (node (ref "P6") (pin "17") (pinfunction "17_17") (pintype "passive"))
      (node (ref "QD1") (pin "5") (pinfunction "CS_5") (pintype "passive"))
    )
    (net (code "18") (name "/IO23") (class "Default")
      (node (ref "MD1") (pin "37") (pinfunction "IO23_37") (pintype "bidirectional"))
      (node (ref "P6") (pin "19") (pinfunction "19_19") (pintype "passive"))
      (node (ref "QD1") (pin "6") (pinfunction "SDA_6") (pintype "passive"))
      (node (ref "U12") (pin "14") (pinfunction "DIN_14") (pintype "passive"))
    )
    (net (code "19") (name "/IO25") (class "Default")
      (node (ref "MD1") (pin "10") (pinfunction "IO25_10") (pintype "bidirectional"))
      (node (ref "P6") (pin "21") (pinfunction "21_21") (pintype "passive"))
      (node (ref "QD1") (pin "7") (pinfunction "SDO_7") (pintype "passive"))
      (node (ref "U12") (pin "12") (pinfunction "DOUT_12") (pintype "passive"))
    )
    (net (code "20") (name "/IO32") (class "Default")
      (node (ref "C16") (pin "2") (pinfunction "2_2") (pintype "passive"))
      (node (ref "MD1") (pin "8") (pinfunction "IO32_8") (pintype "bidirectional"))
      (node (ref "P6") (pin "23") (pinfunction "23_23") (pintype "passive"))
      (node (ref "X1") (pin "2") (pinfunction "OSC2_2") (pintype "passive"))
    )
    (net (code "21") (name "/IO33") (class "Default")
      (node (ref "C15") (pin "2") (pinfunction "2_2") (pintype "passive"))
      (node (ref "MD1") (pin "9") (pinfunction "IO33_9") (pintype "bidirectional"))
      (node (ref "P6") (pin "25") (pinfunction "25_25") (pintype "passive"))
      (node (ref "X1") (pin "1") (pinfunction "OSC1_1") (pintype "passive"))
    )
    (net (code "22") (name "/MCU_RX1") (class "Default")
      (node (ref "JP3") (pin "2") (pinfunction "2_2") (pintype "passive"))
      (node (ref "MD1") (pin "34") (pinfunction "RXD0_34") (pintype "bidirectional"))
    )
    (net (code "23") (name "/MCU_TX1") (class "Default")
      (node (ref "JP4") (pin "2") (pinfunction "2_2") (pintype "passive"))
      (node (ref "MD1") (pin "35") (pinfunction "TXD0_35") (pintype "bidirectional"))
    )
    (net (code "24") (name "/QA") (class "Default")
      (node (ref "P7") (pin "8") (pinfunction "8_8") (pintype "passive"))
      (node (ref "U10") (pin "9") (pinfunction "A8_9") (pintype "input"))
      (node (ref "U11") (pin "15") (pinfunction "QA_15") (pintype "tri_state"))
    )
    (net (code "25") (name "/QB") (class "Default")
      (node (ref "P7") (pin "7") (pinfunction "7_7") (pintype "passive"))
      (node (ref "U10") (pin "8") (pinfunction "A7_8") (pintype "input"))
      (node (ref "U11") (pin "1") (pinfunction "QB_1") (pintype "tri_state"))
    )
    (net (code "26") (name "/QC") (class "Default")
      (node (ref "P7") (pin "6") (pinfunction "6_6") (pintype "passive"))
      (node (ref "U10") (pin "7") (pinfunction "A6_7") (pintype "input"))
      (node (ref "U11") (pin "2") (pinfunction "QC_2") (pintype "tri_state"))
    )
    (net (code "27") (name "/QD") (class "Default")
      (node (ref "P7") (pin "5") (pinfunction "5_5") (pintype "passive"))
      (node (ref "U10") (pin "6") (pinfunction "A5_6") (pintype "input"))
      (node (ref "U11") (pin "3") (pinfunction "QD_3") (pintype "tri_state"))
    )
    (net (code "28") (name "/QE") (class "Default")
      (node (ref "P7") (pin "4") (pinfunction "4_4") (pintype "passive"))
      (node (ref "U10") (pin "5") (pinfunction "A4_5") (pintype "input"))
      (node (ref "U11") (pin "4") (pinfunction "QE_4") (pintype "tri_state"))
    )
    (net (code "29") (name "/QF") (class "Default")
      (node (ref "P7") (pin "3") (pinfunction "3_3") (pintype "passive"))
      (node (ref "U10") (pin "4") (pinfunction "A3_4") (pintype "input"))
      (node (ref "U11") (pin "5") (pinfunction "QF_5") (pintype "tri_state"))
    )
    (net (code "30") (name "/QG") (class "Default")
      (node (ref "P7") (pin "2") (pinfunction "2_2") (pintype "passive"))
      (node (ref "U10") (pin "3") (pinfunction "A2_3") (pintype "input"))
      (node (ref "U11") (pin "6") (pinfunction "QG_6") (pintype "tri_state"))
    )
    (net (code "31") (name "/QH") (class "Default")
      (node (ref "P7") (pin "1") (pinfunction "1_1") (pintype "passive"))
      (node (ref "U10") (pin "2") (pinfunction "A1_2") (pintype "input"))
      (node (ref "U11") (pin "7") (pinfunction "QH_7") (pintype "tri_state"))
    )
    (net (code "32") (name "/RCLK") (class "Default")
      (node (ref "C14") (pin "1") (pinfunction "1_1") (pintype "passive"))
      (node (ref "MD1") (pin "11") (pinfunction "IO26_11") (pintype "bidirectional"))
      (node (ref "R22") (pin "1") (pinfunction "1_1") (pintype "passive"))
      (node (ref "U11") (pin "12") (pinfunction "RCLK_12") (pintype "input"))
    )
    (net (code "33") (name "/REL1") (class "Default")
      (node (ref "U10") (pin "14") (pinfunction "Y5_14") (pintype "tri_state"))
      (node (ref "U3") (pin "1") (pinfunction "A_1") (pintype "passive"))
    )
    (net (code "34") (name "/REL2") (class "Default")
      (node (ref "U10") (pin "13") (pinfunction "Y6_13") (pintype "tri_state"))
      (node (ref "U4") (pin "1") (pinfunction "A_1") (pintype "passive"))
    )
    (net (code "35") (name "/RTS") (class "Default")
      (node (ref "JP5") (pin "1") (pinfunction "1_1") (pintype "passive"))
      (node (ref "Q5") (pin "2") (pinfunction "E_2") (pintype "passive"))
      (node (ref "R21") (pin "1") (pinfunction "1_1") (pintype "passive"))
      (node (ref "U6") (pin "3") (pinfunction "RTS#_3") (pintype "passive"))
    )
    (net (code "36") (name "/RXD") (class "Default")
      (node (ref "JP4") (pin "1") (pinfunction "1_1") (pintype "passive"))
      (node (ref "U6") (pin "5") (pinfunction "RXD_5") (pintype "passive"))
    )
    (net (code "37") (name "/SD0") (class "Default")
      (node (ref "MD1") (pin "21") (pinfunction "SD0_21") (pintype "bidirectional"))
      (node (ref "P6") (pin "5") (pinfunction "5_5") (pintype "passive"))
    )
    (net (code "38") (name "/SD1") (class "Default")
      (node (ref "MD1") (pin "22") (pinfunction "SD1_22") (pintype "bidirectional"))
      (node (ref "P6") (pin "7") (pinfunction "7_7") (pintype "passive"))
    )
    (net (code "39") (name "/SD2") (class "Default")
      (node (ref "MD1") (pin "17") (pinfunction "SD2_17") (pintype "bidirectional"))
      (node (ref "P6") (pin "9") (pinfunction "9_9") (pintype "passive"))
    )
    (net (code "40") (name "/SD3") (class "Default")
      (node (ref "MD1") (pin "18") (pinfunction "SD3_18") (pintype "bidirectional"))
      (node (ref "P6") (pin "11") (pinfunction "11_11") (pintype "passive"))
    )
    (net (code "41") (name "/SENSOR_N") (class "Default")
      (node (ref "MD1") (pin "5") (pinfunction "SENSOR_VN_5") (pintype "bidirectional"))
      (node (ref "P6") (pin "1") (pinfunction "1_1") (pintype "passive"))
    )
    (net (code "42") (name "/SENSOR_P") (class "Default")
      (node (ref "MD1") (pin "4") (pinfunction "SENSOR_VP_4") (pintype "bidirectional"))
      (node (ref "P6") (pin "3") (pinfunction "3_3") (pintype "passive"))
    )
    (net (code "43") (name "/SER") (class "Default")
      (node (ref "MD1") (pin "6") (pinfunction "IO34_6") (pintype "bidirectional"))
      (node (ref "U11") (pin "14") (pinfunction "SER_14") (pintype "input"))
    )
    (net (code "44") (name "/SRCLK") (class "Default")
      (node (ref "MD1") (pin "7") (pinfunction "IO35_7") (pintype "bidirectional"))
      (node (ref "U11") (pin "11") (pinfunction "SRCLK_11") (pintype "input"))
    )
    (net (code "45") (name "/TXD") (class "Default")
      (node (ref "JP3") (pin "1") (pinfunction "1_1") (pintype "passive"))
      (node (ref "U6") (pin "1") (pinfunction "TXD_1") (pintype "passive"))
    )
    (net (code "46") (name "/USB_D_N") (class "Default")
      (node (ref "U6") (pin "16") (pinfunction "USBDM_16") (pintype "passive"))
      (node (ref "USB1") (pin "2") (pinfunction "D-_2") (pintype "passive"))
    )
    (net (code "47") (name "/USB_D_P") (class "Default")
      (node (ref "U6") (pin "15") (pinfunction "USBDP_15") (pintype "passive"))
      (node (ref "USB1") (pin "3") (pinfunction "D+_3") (pintype "passive"))
    )
    (net (code "48") (name "/X+") (class "Default")
      (node (ref "QD1") (pin "15") (pinfunction "XL_15") (pintype "passive"))
      (node (ref "U12") (pin "2") (pinfunction "X+_2") (pintype "passive"))
    )
    (net (code "49") (name "/X-") (class "Default")
      (node (ref "QD1") (pin "17") (pinfunction "XR_17") (pintype "passive"))
      (node (ref "U12") (pin "4") (pinfunction "X-_4") (pintype "passive"))
    )
    (net (code "50") (name "/Y+") (class "Default")
      (node (ref "QD1") (pin "18") (pinfunction "YD_18") (pintype "passive"))
      (node (ref "U12") (pin "3") (pinfunction "Y+_3") (pintype "passive"))
    )
    (net (code "51") (name "/Y-") (class "Default")
      (node (ref "QD1") (pin "16") (pinfunction "YU_16") (pintype "passive"))
      (node (ref "U12") (pin "5") (pinfunction "Y-_5") (pintype "passive"))
    )
    (net (code "52") (name "/touch7") (class "Default")
      (node (ref "MD1") (pin "12") (pinfunction "IO27_12") (pintype "bidirectional"))
    )
    (net (code "53") (name "3V3") (class "Default")
      (node (ref "C13") (pin "2") (pinfunction "2_2") (pintype "passive"))
      (node (ref "C19") (pin "2") (pinfunction "2_2") (pintype "passive"))
      (node (ref "C5") (pin "2") (pinfunction "2_2") (pintype "passive"))
      (node (ref "CN1") (pin "4") (pinfunction "VDD_4") (pintype "passive"))
      (node (ref "FB1") (pin "2") (pinfunction "2_2") (pintype "passive"))
      (node (ref "FB5") (pin "1") (pinfunction "1_1") (pintype "passive"))
      (node (ref "MD1") (pin "2") (pinfunction "VDD33_2") (pintype "power_in"))
      (node (ref "P6") (pin "4") (pinfunction "4_4") (pintype "passive"))
      (node (ref "QD1") (pin "10") (pinfunction "LEDA_10") (pintype "passive"))
      (node (ref "QD1") (pin "9") (pinfunction "VDD_9") (pintype "passive"))
      (node (ref "R24") (pin "2") (pinfunction "2_2") (pintype "passive"))
      (node (ref "R25") (pin "1") (pinfunction "1_1") (pintype "passive"))
      (node (ref "R26") (pin "1") (pinfunction "1_1") (pintype "passive"))
      (node (ref "R27") (pin "1") (pinfunction "1_1") (pintype "passive"))
      (node (ref "R28") (pin "1") (pinfunction "1_1") (pintype "passive"))
      (node (ref "R29") (pin "1") (pinfunction "1_1") (pintype "passive"))
      (node (ref "R30") (pin "2") (pinfunction "2_2") (pintype "passive"))
      (node (ref "R31") (pin "1") (pinfunction "1_1") (pintype "passive"))
      (node (ref "R32") (pin "1") (pinfunction "1_1") (pintype "passive"))
      (node (ref "R34") (pin "2") (pinfunction "2_2") (pintype "passive"))
      (node (ref "R36") (pin "2") (pinfunction "2_2") (pintype "passive"))
    )
    (net (code "54") (name "3V3A") (class "Default")
      (node (ref "C17") (pin "2") (pinfunction "2_2") (pintype "passive"))
      (node (ref "C18") (pin "1") (pinfunction "1_1") (pintype "passive"))
      (node (ref "FB5") (pin "2") (pinfunction "2_2") (pintype "passive"))
      (node (ref "U12") (pin "1") (pinfunction "+VCC_1") (pintype "passive"))
      (node (ref "U12") (pin "10") (pinfunction "+VCC_10") (pintype "passive"))
      (node (ref "U12") (pin "9") (pinfunction "VREF_9") (pintype "passive"))
    )
    (net (code "55") (name "5V0") (class "Default")
      (node (ref "C10") (pin "2") (pinfunction "2_2") (pintype "passive"))
      (node (ref "C11") (pin "2") (pinfunction "2_2") (pintype "passive"))
      (node (ref "C12") (pin "1") (pinfunction "1_1") (pintype "passive"))
      (node (ref "C2") (pin "1") (pinfunction "1_1") (pintype "passive"))
      (node (ref "C3") (pin "2") (pinfunction "2_2") (pintype "passive"))
      (node (ref "C8") (pin "2") (pinfunction "2_2") (pintype "passive"))
      (node (ref "C9") (pin "2") (pinfunction "2_2") (pintype "passive"))
      (node (ref "D1") (pin "2") (pinfunction "2_2") (pintype "passive"))
      (node (ref "D9") (pin "2") (pinfunction "K_2") (pintype "passive"))
      (node (ref "FB2") (pin "1") (pinfunction "1_1") (pintype "passive"))
      (node (ref "FB3") (pin "2") (pinfunction "2_2") (pintype "passive"))
      (node (ref "L1") (pin "2") (pinfunction "2_2") (pintype "passive"))
      (node (ref "P6") (pin "2") (pinfunction "2_2") (pintype "passive"))
      (node (ref "R1") (pin "2") (pinfunction "2_2") (pintype "passive"))
      (node (ref "U1") (pin "4") (pinfunction "FB_4") (pintype "input"))
      (node (ref "U10") (pin "20") (pinfunction "VCC_20") (pintype "power_in"))
      (node (ref "U11") (pin "10") (pinfunction "~{SRCLR}_10") (pintype "input"))
      (node (ref "U11") (pin "16") (pinfunction "VCC_16") (pintype "power_in"))
      (node (ref "U2") (pin "3") (pinfunction "IN_3") (pintype "passive"))
      (node (ref "U6") (pin "20") (pinfunction "VCC_20") (pintype "passive"))
      (node (ref "U9") (pin "1") (pinfunction "+VIN_1") (pintype "passive"))
    )
    (net (code "56") (name "12V0") (class "Default")
      (node (ref "C1") (pin "1") (pinfunction "1_1") (pintype "passive"))
      (node (ref "D3") (pin "2") (pinfunction "K_2") (pintype "passive"))
      (node (ref "U1") (pin "1") (pinfunction "VIN_1") (pintype "power_in"))
    )
    (net (code "57") (name "ADC_GND") (class "Default")
      (node (ref "C17") (pin "1") (pinfunction "1_1") (pintype "passive"))
      (node (ref "C18") (pin "2") (pinfunction "2_2") (pintype "passive"))
      (node (ref "FB6") (pin "2") (pinfunction "2_2") (pintype "passive"))
      (node (ref "U12") (pin "6") (pinfunction "GND_6") (pintype "passive"))
    )
    (net (code "58") (name "GND") (class "Default")
      (node (ref "C1") (pin "2") (pinfunction "2_2") (pintype "passive"))
      (node (ref "C10") (pin "1") (pinfunction "1_1") (pintype "passive"))
      (node (ref "C11") (pin "1") (pinfunction "1_1") (pintype "passive"))
      (node (ref "C12") (pin "2") (pinfunction "2_2") (pintype "passive"))
      (node (ref "C13") (pin "1") (pinfunction "1_1") (pintype "passive"))
      (node (ref "C14") (pin "2") (pinfunction "2_2") (pintype "passive"))
      (node (ref "C15") (pin "1") (pinfunction "1_1") (pintype "passive"))
      (node (ref "C16") (pin "1") (pinfunction "1_1") (pintype "passive"))
      (node (ref "C19") (pin "1") (pinfunction "1_1") (pintype "passive"))
      (node (ref "C2") (pin "2") (pinfunction "2_2") (pintype "passive"))
      (node (ref "C20") (pin "1") (pinfunction "1_1") (pintype "passive"))
      (node (ref "C3") (pin "1") (pinfunction "1_1") (pintype "passive"))
      (node (ref "C4") (pin "1") (pinfunction "1_1") (pintype "passive"))
      (node (ref "C5") (pin "1") (pinfunction "1_1") (pintype "passive"))
      (node (ref "C6") (pin "2") (pinfunction "2_2") (pintype "passive"))
      (node (ref "C7") (pin "1") (pinfunction "1_1") (pintype "passive"))
      (node (ref "C8") (pin "1") (pinfunction "1_1") (pintype "passive"))
      (node (ref "C9") (pin "1") (pinfunction "1_1") (pintype "passive"))
      (node (ref "CN1") (pin "10") (pinfunction "GND_10") (pintype "passive"))
      (node (ref "CN1") (pin "11") (pinfunction "EP_11") (pintype "passive"))
      (node (ref "CN1") (pin "12") (pinfunction "EP_12") (pintype "passive"))
      (node (ref "CN1") (pin "13") (pinfunction "EP_13") (pintype "passive"))
      (node (ref "CN1") (pin "6") (pinfunction "GND_6") (pintype "passive"))
      (node (ref "D11") (pin "2") (pinfunction "K_2") (pintype "passive"))
      (node (ref "D8") (pin "1") (pinfunction "A_1") (pintype "passive"))
      (node (ref "D9") (pin "1") (pinfunction "A_1") (pintype "passive"))
      (node (ref "FB4") (pin "1") (pinfunction "1_1") (pintype "passive"))
      (node (ref "FB6") (pin "1") (pinfunction "1_1") (pintype "passive"))
      (node (ref "MD1") (pin "1") (pinfunction "GND_1") (pintype "power_in"))
      (node (ref "MD1") (pin "15") (pinfunction "GND_15") (pintype "power_in"))
      (node (ref "MD1") (pin "38") (pinfunction "GND_38") (pintype "power_in"))
      (node (ref "MD1") (pin "39") (pinfunction "GND_39") (pintype "power_in"))
      (node (ref "P4") (pin "1") (pinfunction "1_1") (pintype "passive"))
      (node (ref "P6") (pin "27") (pinfunction "27_27") (pintype "passive"))
      (node (ref "P6") (pin "28") (pinfunction "28_28") (pintype "passive"))
      (node (ref "P7") (pin "9") (pinfunction "9_9") (pintype "passive"))
      (node (ref "Q7") (pin "2") (pinfunction "E_2") (pintype "passive"))
      (node (ref "Q8") (pin "2") (pinfunction "E_2") (pintype "passive"))
      (node (ref "QD1") (pin "1") (pinfunction "GND_1") (pintype "passive"))
      (node (ref "QD1") (pin "8") (pinfunction "GND_8") (pintype "passive"))
      (node (ref "R11") (pin "2") (pinfunction "2_2") (pintype "passive"))
      (node (ref "R22") (pin "2") (pinfunction "2_2") (pintype "passive"))
      (node (ref "R23") (pin "1") (pinfunction "1_1") (pintype "passive"))
      (node (ref "R9") (pin "2") (pinfunction "2_2") (pintype "passive"))
      (node (ref "S2") (pin "1") (pinfunction "1_1") (pintype "passive"))
      (node (ref "S3") (pin "1") (pinfunction "1_1") (pintype "passive"))
      (node (ref "U1") (pin "3") (pinfunction "GND_3") (pintype "power_in"))
      (node (ref "U1") (pin "5") (pinfunction "~{ON}/OFF_5") (pintype "input"))
      (node (ref "U10") (pin "1") (pinfunction "~{OE}1_1") (pintype "input"))
      (node (ref "U10") (pin "10") (pinfunction "GND_10") (pintype "power_in"))
      (node (ref "U10") (pin "19") (pinfunction "~{OE}2_19") (pintype "input"))
      (node (ref "U11") (pin "13") (pinfunction "~{OE}_13") (pintype "input"))
      (node (ref "U11") (pin "8") (pinfunction "GND_8") (pintype "power_in"))
      (node (ref "U2") (pin "1") (pinfunction "GND_1") (pintype "passive"))
      (node (ref "U6") (pin "18") (pinfunction "GND_18") (pintype "passive"))
      (node (ref "U6") (pin "21") (pinfunction "GND_21") (pintype "passive"))
      (node (ref "U6") (pin "25") (pinfunction "AGND_25") (pintype "passive"))
      (node (ref "U6") (pin "26") (pinfunction "TEST_26") (pintype "passive"))
      (node (ref "U6") (pin "7") (pinfunction "GND_7") (pintype "passive"))
      (node (ref "U9") (pin "2") (pinfunction "-VIN_2") (pintype "passive"))
      (node (ref "USB1") (pin "5") (pinfunction "GND_5") (pintype "passive"))
    )
    (net (code "59") (name "GND_ISOLATED") (class "Default")
      (node (ref "JP2") (pin "3") (pinfunction "3_3") (pintype "passive"))
      (node (ref "U9") (pin "7") (pinfunction "+VOUT_7") (pintype "passive"))
    )
    (net (code "60") (name "GNDx") (class "Default")
      (node (ref "JP2") (pin "2") (pinfunction "2_2") (pintype "passive"))
      (node (ref "Q1") (pin "2") (pinfunction "E_2") (pintype "passive"))
      (node (ref "Q2") (pin "2") (pinfunction "E_2") (pintype "passive"))
      (node (ref "R10") (pin "1") (pinfunction "1_1") (pintype "passive"))
      (node (ref "R7") (pin "1") (pinfunction "1_1") (pintype "passive"))
    )
    (net (code "61") (name "Net-(CN1-CD)") (class "Default")
      (node (ref "CN1") (pin "9") (pinfunction "CD_9") (pintype "passive"))
      (node (ref "R35") (pin "2") (pinfunction "2_2") (pintype "passive"))
    )
    (net (code "62") (name "Net-(D2-K)") (class "Default")
      (node (ref "D2") (pin "2") (pinfunction "K_2") (pintype "passive"))
      (node (ref "R2") (pin "2") (pinfunction "2_2") (pintype "passive"))
    )
    (net (code "63") (name "Net-(D3-A)") (class "Default")
      (node (ref "D3") (pin "1") (pinfunction "A_1") (pintype "passive"))
      (node (ref "S1") (pin "2") (pinfunction "NO_2") (pintype "passive"))
    )
    (net (code "64") (name "Net-(D4-K)") (class "Default")
      (node (ref "D4") (pin "2") (pinfunction "K_2") (pintype "passive"))
      (node (ref "R3") (pin "2") (pinfunction "2_2") (pintype "passive"))
    )
    (net (code "65") (name "Net-(D5-A)") (class "Default")
      (node (ref "D5") (pin "1") (pinfunction "A_1") (pintype "passive"))
      (node (ref "K1") (pin "5") (pinfunction "T2_5") (pintype "passive"))
      (node (ref "Q1") (pin "3") (pinfunction "C_3") (pintype "passive"))
      (node (ref "R2") (pin "1") (pinfunction "1_1") (pintype "passive"))
    )
    (net (code "66") (name "Net-(D7-A)") (class "Default")
      (node (ref "D7") (pin "1") (pinfunction "A_1") (pintype "passive"))
      (node (ref "K2") (pin "5") (pinfunction "T2_5") (pintype "passive"))
      (node (ref "Q2") (pin "3") (pinfunction "C_3") (pintype "passive"))
      (node (ref "R3") (pin "1") (pinfunction "1_1") (pintype "passive"))
    )
    (net (code "67") (name "Net-(D8-K)") (class "Default")
      (node (ref "D8") (pin "2") (pinfunction "K_2") (pintype "passive"))
      (node (ref "L1") (pin "1") (pinfunction "1_1") (pintype "passive"))
      (node (ref "U1") (pin "2") (pinfunction "OUT_2") (pintype "power_in"))
    )
    (net (code "68") (name "Net-(D11-A)") (class "Default")
      (node (ref "D11") (pin "1") (pinfunction "A_1") (pintype "passive"))
      (node (ref "R1") (pin "1") (pinfunction "1_1") (pintype "passive"))
    )
    (net (code "69") (name "Net-(D12-A)") (class "Default")
      (node (ref "D12") (pin "1") (pinfunction "A_1") (pintype "passive"))
      (node (ref "R14") (pin "1") (pinfunction "1_1") (pintype "passive"))
    )
    (net (code "70") (name "Net-(D12-K)") (class "Default")
      (node (ref "D12") (pin "2") (pinfunction "K_2") (pintype "passive"))
      (node (ref "U6") (pin "23") (pinfunction "CBUS0_23") (pintype "passive"))
    )
    (net (code "71") (name "Net-(D13-A)") (class "Default")
      (node (ref "D13") (pin "1") (pinfunction "A_1") (pintype "passive"))
      (node (ref "R15") (pin "1") (pinfunction "1_1") (pintype "passive"))
    )
    (net (code "72") (name "Net-(D13-K)") (class "Default")
      (node (ref "D13") (pin "2") (pinfunction "K_2") (pintype "passive"))
      (node (ref "U6") (pin "22") (pinfunction "CBUS1_22") (pintype "passive"))
    )
    (net (code "73") (name "Net-(D16-A)") (class "Default")
      (node (ref "D16") (pin "1") (pinfunction "A_1") (pintype "passive"))
      (node (ref "U10") (pin "18") (pinfunction "Y1_18") (pintype "tri_state"))
    )
    (net (code "74") (name "Net-(D16-K)") (class "Default")
      (node (ref "D16") (pin "2") (pinfunction "K_2") (pintype "passive"))
      (node (ref "D17") (pin "2") (pinfunction "K_2") (pintype "passive"))
      (node (ref "D18") (pin "2") (pinfunction "K_2") (pintype "passive"))
      (node (ref "D19") (pin "2") (pinfunction "K_2") (pintype "passive"))
      (node (ref "R23") (pin "2") (pinfunction "2_2") (pintype "passive"))
    )
    (net (code "75") (name "Net-(D17-A)") (class "Default")
      (node (ref "D17") (pin "1") (pinfunction "A_1") (pintype "passive"))
      (node (ref "U10") (pin "17") (pinfunction "Y2_17") (pintype "tri_state"))
    )
    (net (code "76") (name "Net-(D18-A)") (class "Default")
      (node (ref "D18") (pin "1") (pinfunction "A_1") (pintype "passive"))
      (node (ref "U10") (pin "16") (pinfunction "Y3_16") (pintype "tri_state"))
    )
    (net (code "77") (name "Net-(D19-A)") (class "Default")
      (node (ref "D19") (pin "1") (pinfunction "A_1") (pintype "passive"))
      (node (ref "U10") (pin "15") (pinfunction "Y4_15") (pintype "tri_state"))
    )
    (net (code "78") (name "Net-(FB2-Pad2)") (class "Default")
      (node (ref "FB2") (pin "2") (pinfunction "2_2") (pintype "passive"))
      (node (ref "JP1") (pin "1") (pinfunction "1_1") (pintype "passive"))
    )
    (net (code "79") (name "Net-(FB4-Pad2)") (class "Default")
      (node (ref "FB4") (pin "2") (pinfunction "2_2") (pintype "passive"))
      (node (ref "JP2") (pin "1") (pinfunction "1_1") (pintype "passive"))
    )
    (net (code "80") (name "Net-(K1-COM)") (class "Default")
      (node (ref "K1") (pin "1") (pinfunction "COM_1") (pintype "passive"))
      (node (ref "P1") (pin "2") (pinfunction "2_2") (pintype "passive"))
    )
    (net (code "81") (name "Net-(K1-NC)") (class "Default")
      (node (ref "K1") (pin "2") (pinfunction "NC_2") (pintype "passive"))
      (node (ref "P1") (pin "1") (pinfunction "1_1") (pintype "passive"))
    )
    (net (code "82") (name "Net-(K1-NO)") (class "Default")
      (node (ref "K1") (pin "3") (pinfunction "NO_3") (pintype "passive"))
      (node (ref "P1") (pin "3") (pinfunction "3_3") (pintype "passive"))
    )
    (net (code "83") (name "Net-(K2-COM)") (class "Default")
      (node (ref "K2") (pin "1") (pinfunction "COM_1") (pintype "passive"))
      (node (ref "P2") (pin "2") (pinfunction "2_2") (pintype "passive"))
    )
    (net (code "84") (name "Net-(K2-NC)") (class "Default")
      (node (ref "K2") (pin "2") (pinfunction "NC_2") (pintype "passive"))
      (node (ref "P2") (pin "1") (pinfunction "1_1") (pintype "passive"))
    )
    (net (code "85") (name "Net-(K2-NO)") (class "Default")
      (node (ref "K2") (pin "3") (pinfunction "NO_3") (pintype "passive"))
      (node (ref "P2") (pin "3") (pinfunction "3_3") (pintype "passive"))
    )
    (net (code "86") (name "Net-(Q1-B)") (class "Default")
      (node (ref "Q1") (pin "1") (pinfunction "B_1") (pintype "passive"))
      (node (ref "R5") (pin "2") (pinfunction "2_2") (pintype "passive"))
      (node (ref "R7") (pin "2") (pinfunction "2_2") (pintype "passive"))
    )
    (net (code "87") (name "Net-(Q2-B)") (class "Default")
      (node (ref "Q2") (pin "1") (pinfunction "B_1") (pintype "passive"))
      (node (ref "R10") (pin "2") (pinfunction "2_2") (pintype "passive"))
      (node (ref "R6") (pin "2") (pinfunction "2_2") (pintype "passive"))
    )
    (net (code "88") (name "Net-(Q5-B)") (class "Default")
      (node (ref "Q5") (pin "1") (pinfunction "B_1") (pintype "passive"))
      (node (ref "R20") (pin "2") (pinfunction "2_2") (pintype "passive"))
    )
    (net (code "89") (name "Net-(Q5-C)") (class "Default")
      (node (ref "JP7") (pin "2") (pinfunction "2_2") (pintype "passive"))
      (node (ref "Q5") (pin "3") (pinfunction "C_3") (pintype "passive"))
    )
    (net (code "90") (name "Net-(Q6-B)") (class "Default")
      (node (ref "Q6") (pin "1") (pinfunction "B_1") (pintype "passive"))
      (node (ref "R21") (pin "2") (pinfunction "2_2") (pintype "passive"))
    )
    (net (code "91") (name "Net-(Q6-C)") (class "Default")
      (node (ref "JP8") (pin "2") (pinfunction "2_2") (pintype "passive"))
      (node (ref "Q6") (pin "3") (pinfunction "C_3") (pintype "passive"))
    )
    (net (code "92") (name "Net-(Q7-B)") (class "Default")
      (node (ref "Q7") (pin "1") (pinfunction "B_1") (pintype "passive"))
      (node (ref "R37") (pin "1") (pinfunction "1_1") (pintype "passive"))
    )
    (net (code "93") (name "Net-(Q7-C)") (class "Default")
      (node (ref "Q7") (pin "3") (pinfunction "C_3") (pintype "passive"))
      (node (ref "R33") (pin "2") (pinfunction "2_2") (pintype "passive"))
    )
    (net (code "94") (name "Net-(Q8-B)") (class "Default")
      (node (ref "Q8") (pin "1") (pinfunction "B_1") (pintype "passive"))
      (node (ref "R38") (pin "1") (pinfunction "1_1") (pintype "passive"))
    )
    (net (code "95") (name "Net-(Q8-C)") (class "Default")
      (node (ref "Q8") (pin "3") (pinfunction "C_3") (pintype "passive"))
      (node (ref "R36") (pin "1") (pinfunction "1_1") (pintype "passive"))
      (node (ref "R37") (pin "2") (pinfunction "2_2") (pintype "passive"))
    )
    (net (code "96") (name "Net-(QD1-LEDK1)") (class "Default")
      (node (ref "QD1") (pin "11") (pinfunction "LEDK1_11") (pintype "passive"))
      (node (ref "QD1") (pin "12") (pinfunction "LEDK2_12") (pintype "passive"))
      (node (ref "QD1") (pin "13") (pinfunction "LEDK3_13") (pintype "passive"))
      (node (ref "QD1") (pin "14") (pinfunction "LEDK4_14") (pintype "passive"))
      (node (ref "R33") (pin "1") (pinfunction "1_1") (pintype "passive"))
    )
    (net (code "97") (name "Net-(S1-COMMON)") (class "Default")
      (node (ref "P4") (pin "2") (pinfunction "2_2") (pintype "passive"))
      (node (ref "S1") (pin "1") (pinfunction "COMMON_1") (pintype "passive"))
    )
    (net (code "98") (name "Net-(U2-OUT)") (class "Default")
      (node (ref "C4") (pin "2") (pinfunction "2_2") (pintype "passive"))
      (node (ref "C6") (pin "1") (pinfunction "1_1") (pintype "passive"))
      (node (ref "D1") (pin "1") (pinfunction "1_1") (pintype "passive"))
      (node (ref "FB1") (pin "1") (pinfunction "1_1") (pintype "passive"))
      (node (ref "U2") (pin "2") (pinfunction "OUT_2") (pintype "passive"))
    )
    (net (code "99") (name "Net-(U3-E)") (class "Default")
      (node (ref "R5") (pin "1") (pinfunction "1_1") (pintype "passive"))
      (node (ref "U3") (pin "3") (pinfunction "E_3") (pintype "passive"))
    )
    (net (code "100") (name "Net-(U3-K)") (class "Default")
      (node (ref "R9") (pin "1") (pinfunction "1_1") (pintype "passive"))
      (node (ref "U3") (pin "2") (pinfunction "K_2") (pintype "passive"))
    )
    (net (code "101") (name "Net-(U4-E)") (class "Default")
      (node (ref "R6") (pin "1") (pinfunction "1_1") (pintype "passive"))
      (node (ref "U4") (pin "3") (pinfunction "E_3") (pintype "passive"))
    )
    (net (code "102") (name "Net-(U4-K)") (class "Default")
      (node (ref "R11") (pin "1") (pinfunction "1_1") (pintype "passive"))
      (node (ref "U4") (pin "2") (pinfunction "K_2") (pintype "passive"))
    )
    (net (code "103") (name "Net-(U12-~{PENIRQ})") (class "Default")
      (node (ref "R30") (pin "1") (pinfunction "1_1") (pintype "passive"))
      (node (ref "U12") (pin "11") (pinfunction "~{PENIRQ}_11") (pintype "passive"))
    )
    (net (code "104") (name "Net-(USB1-VCC)") (class "Default")
      (node (ref "FB3") (pin "1") (pinfunction "1_1") (pintype "passive"))
      (node (ref "USB1") (pin "1") (pinfunction "VCC_1") (pintype "passive"))
    )
    (net (code "105") (name "VCCIO") (class "Default")
      (node (ref "C7") (pin "2") (pinfunction "2_2") (pintype "passive"))
      (node (ref "R14") (pin "2") (pinfunction "2_2") (pintype "passive"))
      (node (ref "R15") (pin "2") (pinfunction "2_2") (pintype "passive"))
      (node (ref "U6") (pin "17") (pinfunction "3V3OUT_17") (pintype "passive"))
      (node (ref "U6") (pin "4") (pinfunction "VCCIO_4") (pintype "passive"))
    )
    (net (code "106") (name "VX") (class "Default")
      (node (ref "D2") (pin "1") (pinfunction "A_1") (pintype "passive"))
      (node (ref "D4") (pin "1") (pinfunction "A_1") (pintype "passive"))
      (node (ref "D5") (pin "2") (pinfunction "K_2") (pintype "passive"))
      (node (ref "D7") (pin "2") (pinfunction "K_2") (pintype "passive"))
      (node (ref "JP1") (pin "2") (pinfunction "2_2") (pintype "passive"))
      (node (ref "K1") (pin "4") (pinfunction "T1_4") (pintype "passive"))
      (node (ref "K2") (pin "4") (pinfunction "T1_4") (pintype "passive"))
      (node (ref "U3") (pin "4") (pinfunction "C_4") (pintype "passive"))
      (node (ref "U4") (pin "4") (pinfunction "C_4") (pintype "passive"))
    )
    (net (code "107") (name "V_ISOLATED") (class "Default")
      (node (ref "JP1") (pin "3") (pinfunction "3_3") (pintype "passive"))
      (node (ref "U9") (pin "5") (pinfunction "-VOUT_5") (pintype "passive"))
    )
    (net (code "108") (name "unconnected-(MD1-NC-Pad27)") (class "Default")
      (node (ref "MD1") (pin "27") (pinfunction "NC_27") (pintype "passive+no_connect"))
    )
    (net (code "109") (name "unconnected-(MD1-NC-Pad28)") (class "Default")
      (node (ref "MD1") (pin "28") (pinfunction "NC_28") (pintype "passive+no_connect"))
    )
    (net (code "110") (name "unconnected-(MD1-NC-Pad32)") (class "Default")
      (node (ref "MD1") (pin "32") (pinfunction "NC_32") (pintype "passive+no_connect"))
    )
    (net (code "111") (name "unconnected-(U6-CBUS2-Pad13)") (class "Default")
      (node (ref "U6") (pin "13") (pinfunction "CBUS2_13") (pintype "passive+no_connect"))
    )
    (net (code "112") (name "unconnected-(U6-CBUS3-Pad14)") (class "Default")
      (node (ref "U6") (pin "14") (pinfunction "CBUS3_14") (pintype "passive+no_connect"))
    )
    (net (code "113") (name "unconnected-(U6-CBUS4-Pad12)") (class "Default")
      (node (ref "U6") (pin "12") (pinfunction "CBUS4_12") (pintype "passive+no_connect"))
    )
    (net (code "114") (name "unconnected-(U6-DCD#-Pad10)") (class "Default")
      (node (ref "U6") (pin "10") (pinfunction "DCD#_10") (pintype "passive+no_connect"))
    )
    (net (code "115") (name "unconnected-(U6-DSR#-Pad9)") (class "Default")
      (node (ref "U6") (pin "9") (pinfunction "DSR#_9") (pintype "passive+no_connect"))
    )
    (net (code "116") (name "unconnected-(U6-NC-Pad8)") (class "Default")
      (node (ref "U6") (pin "8") (pinfunction "NC_8") (pintype "passive+no_connect"))
    )
    (net (code "117") (name "unconnected-(U6-NC-Pad24)") (class "Default")
      (node (ref "U6") (pin "24") (pinfunction "NC_24") (pintype "passive+no_connect"))
    )
    (net (code "118") (name "unconnected-(U6-OCSI-Pad27)") (class "Default")
      (node (ref "U6") (pin "27") (pinfunction "OCSI_27") (pintype "passive+no_connect"))
    )
    (net (code "119") (name "unconnected-(U6-OCSO-Pad28)") (class "Default")
      (node (ref "U6") (pin "28") (pinfunction "OCSO_28") (pintype "passive+no_connect"))
    )
    (net (code "120") (name "unconnected-(U6-RESET#-Pad19)") (class "Default")
      (node (ref "U6") (pin "19") (pinfunction "RESET#_19") (pintype "passive+no_connect"))
    )
    (net (code "121") (name "unconnected-(U6-RI#-Pad6)") (class "Default")
      (node (ref "U6") (pin "6") (pinfunction "RI#_6") (pintype "passive+no_connect"))
    )
    (net (code "122") (name "unconnected-(U9-NC-Pad6)") (class "Default")
      (node (ref "U9") (pin "6") (pinfunction "NC_6") (pintype "passive"))
    )
    (net (code "123") (name "unconnected-(U10-Y7-Pad12)") (class "Default")
      (node (ref "U10") (pin "12") (pinfunction "Y7_12") (pintype "tri_state+no_connect"))
    )
    (net (code "124") (name "unconnected-(U10-Y8-Pad11)") (class "Default")
      (node (ref "U10") (pin "11") (pinfunction "Y8_11") (pintype "tri_state+no_connect"))
    )
    (net (code "125") (name "unconnected-(U11-QH'-Pad9)") (class "Default")
      (node (ref "U11") (pin "9") (pinfunction "QH'_9") (pintype "output+no_connect"))
    )
    (net (code "126") (name "unconnected-(U12-AUX-Pad8)") (class "Default")
      (node (ref "U12") (pin "8") (pinfunction "AUX_8") (pintype "passive+no_connect"))
    )
    (net (code "127") (name "unconnected-(U12-BUSY-Pad13)") (class "Default")
      (node (ref "U12") (pin "13") (pinfunction "BUSY_13") (pintype "passive+no_connect"))
    )
    (net (code "128") (name "unconnected-(U12-VBAT-Pad7)") (class "Default")
      (node (ref "U12") (pin "7") (pinfunction "VBAT_7") (pintype "passive+no_connect"))
    )
    (net (code "129") (name "unconnected-(USB1-NC-Pad4)") (class "Default")
      (node (ref "USB1") (pin "4") (pinfunction "NC_4") (pintype "passive+no_connect"))
    )
  )
)
